# valve_indicatorV1.net
KiCad netlist of a schematic drawn in EAGLE
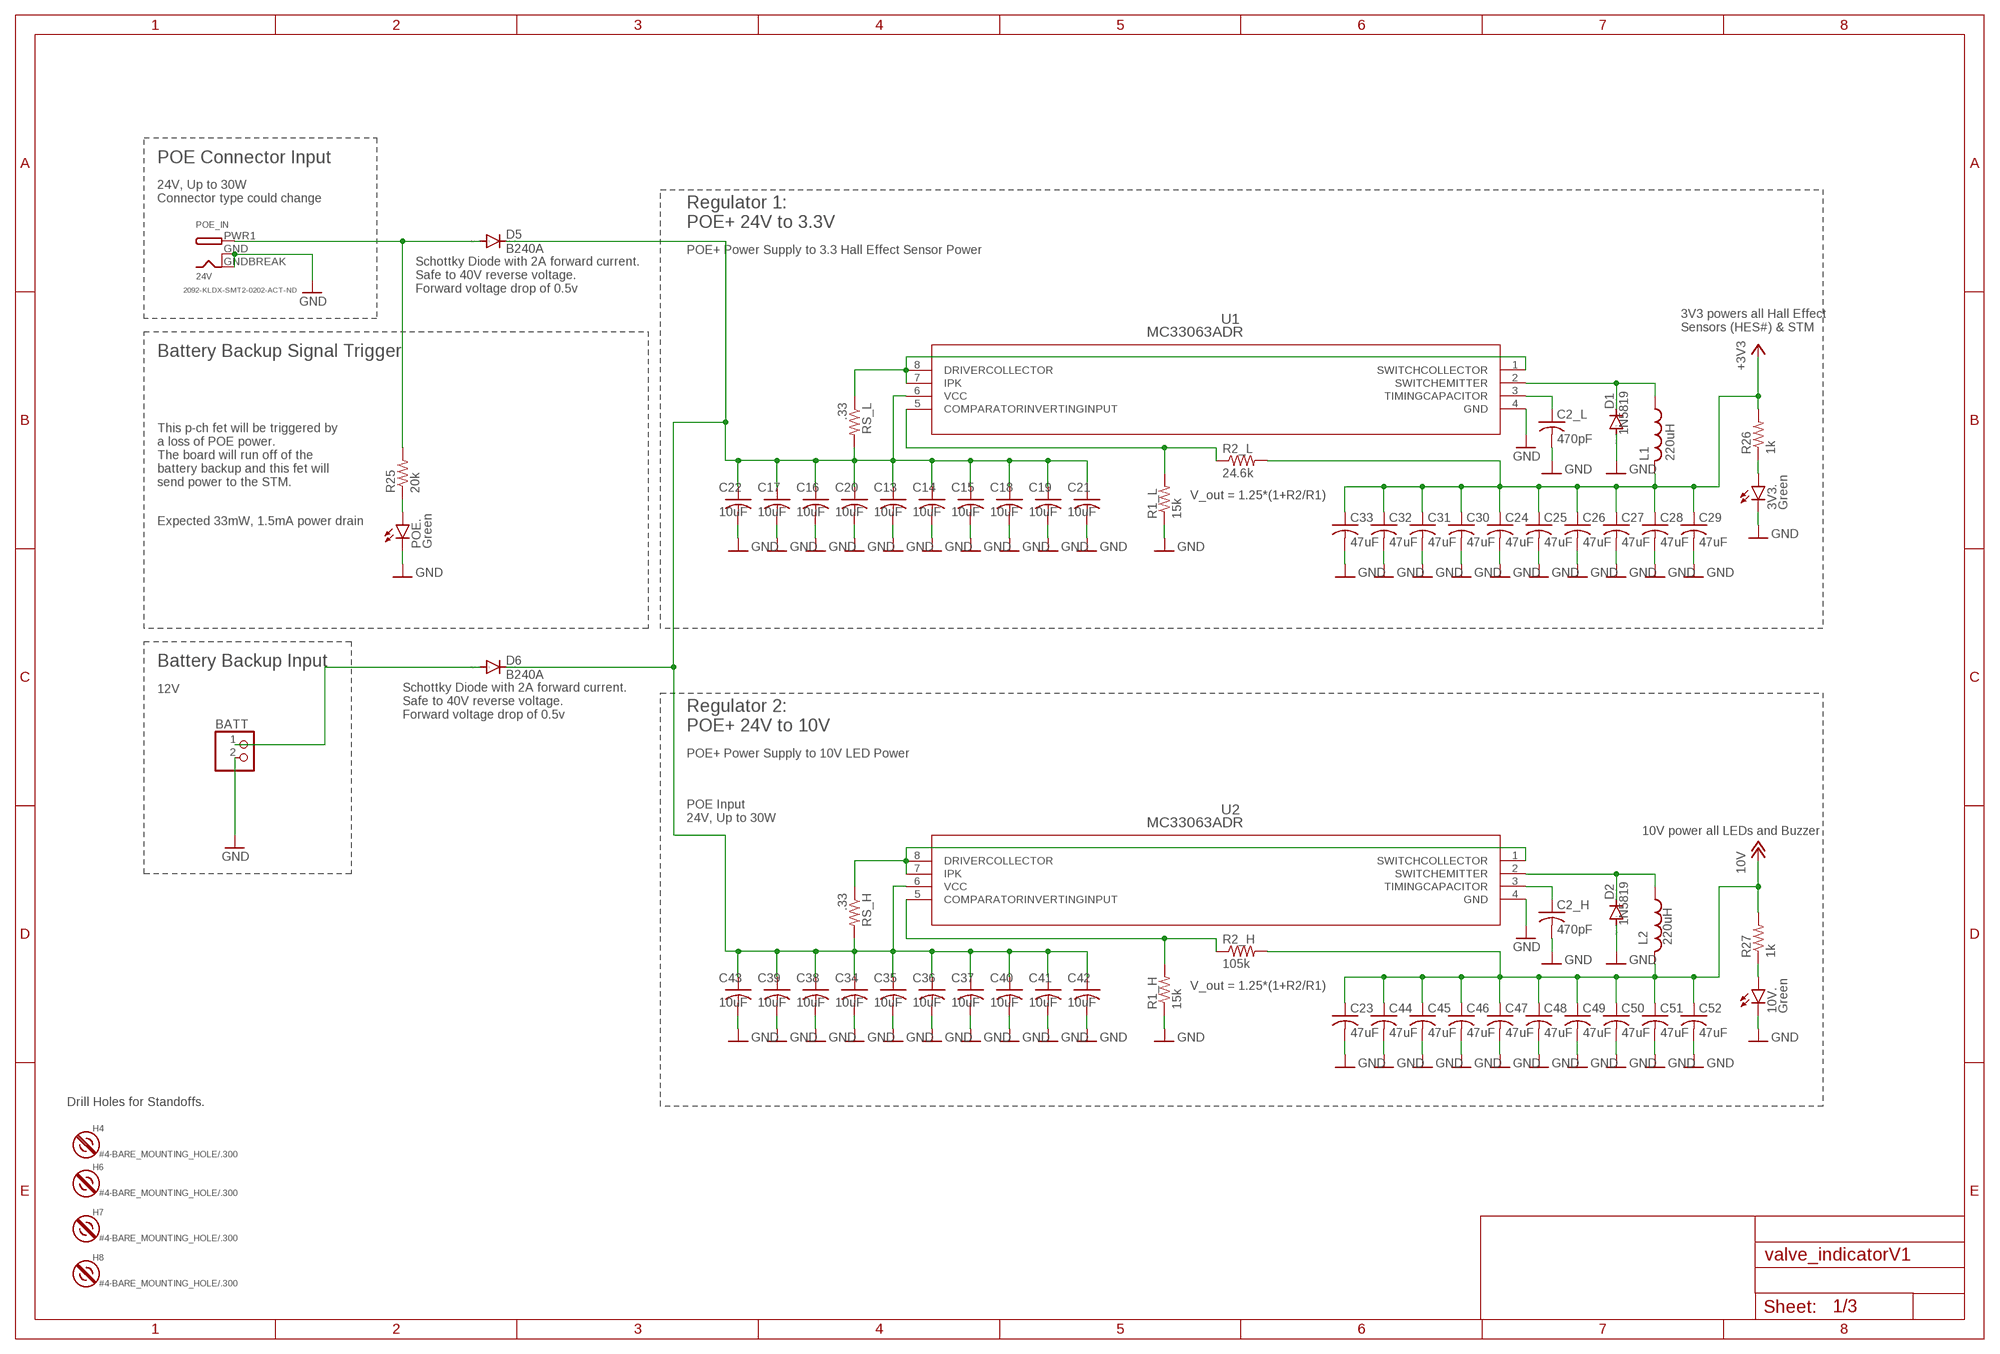
[diagram p0: schematic, sheet 1]
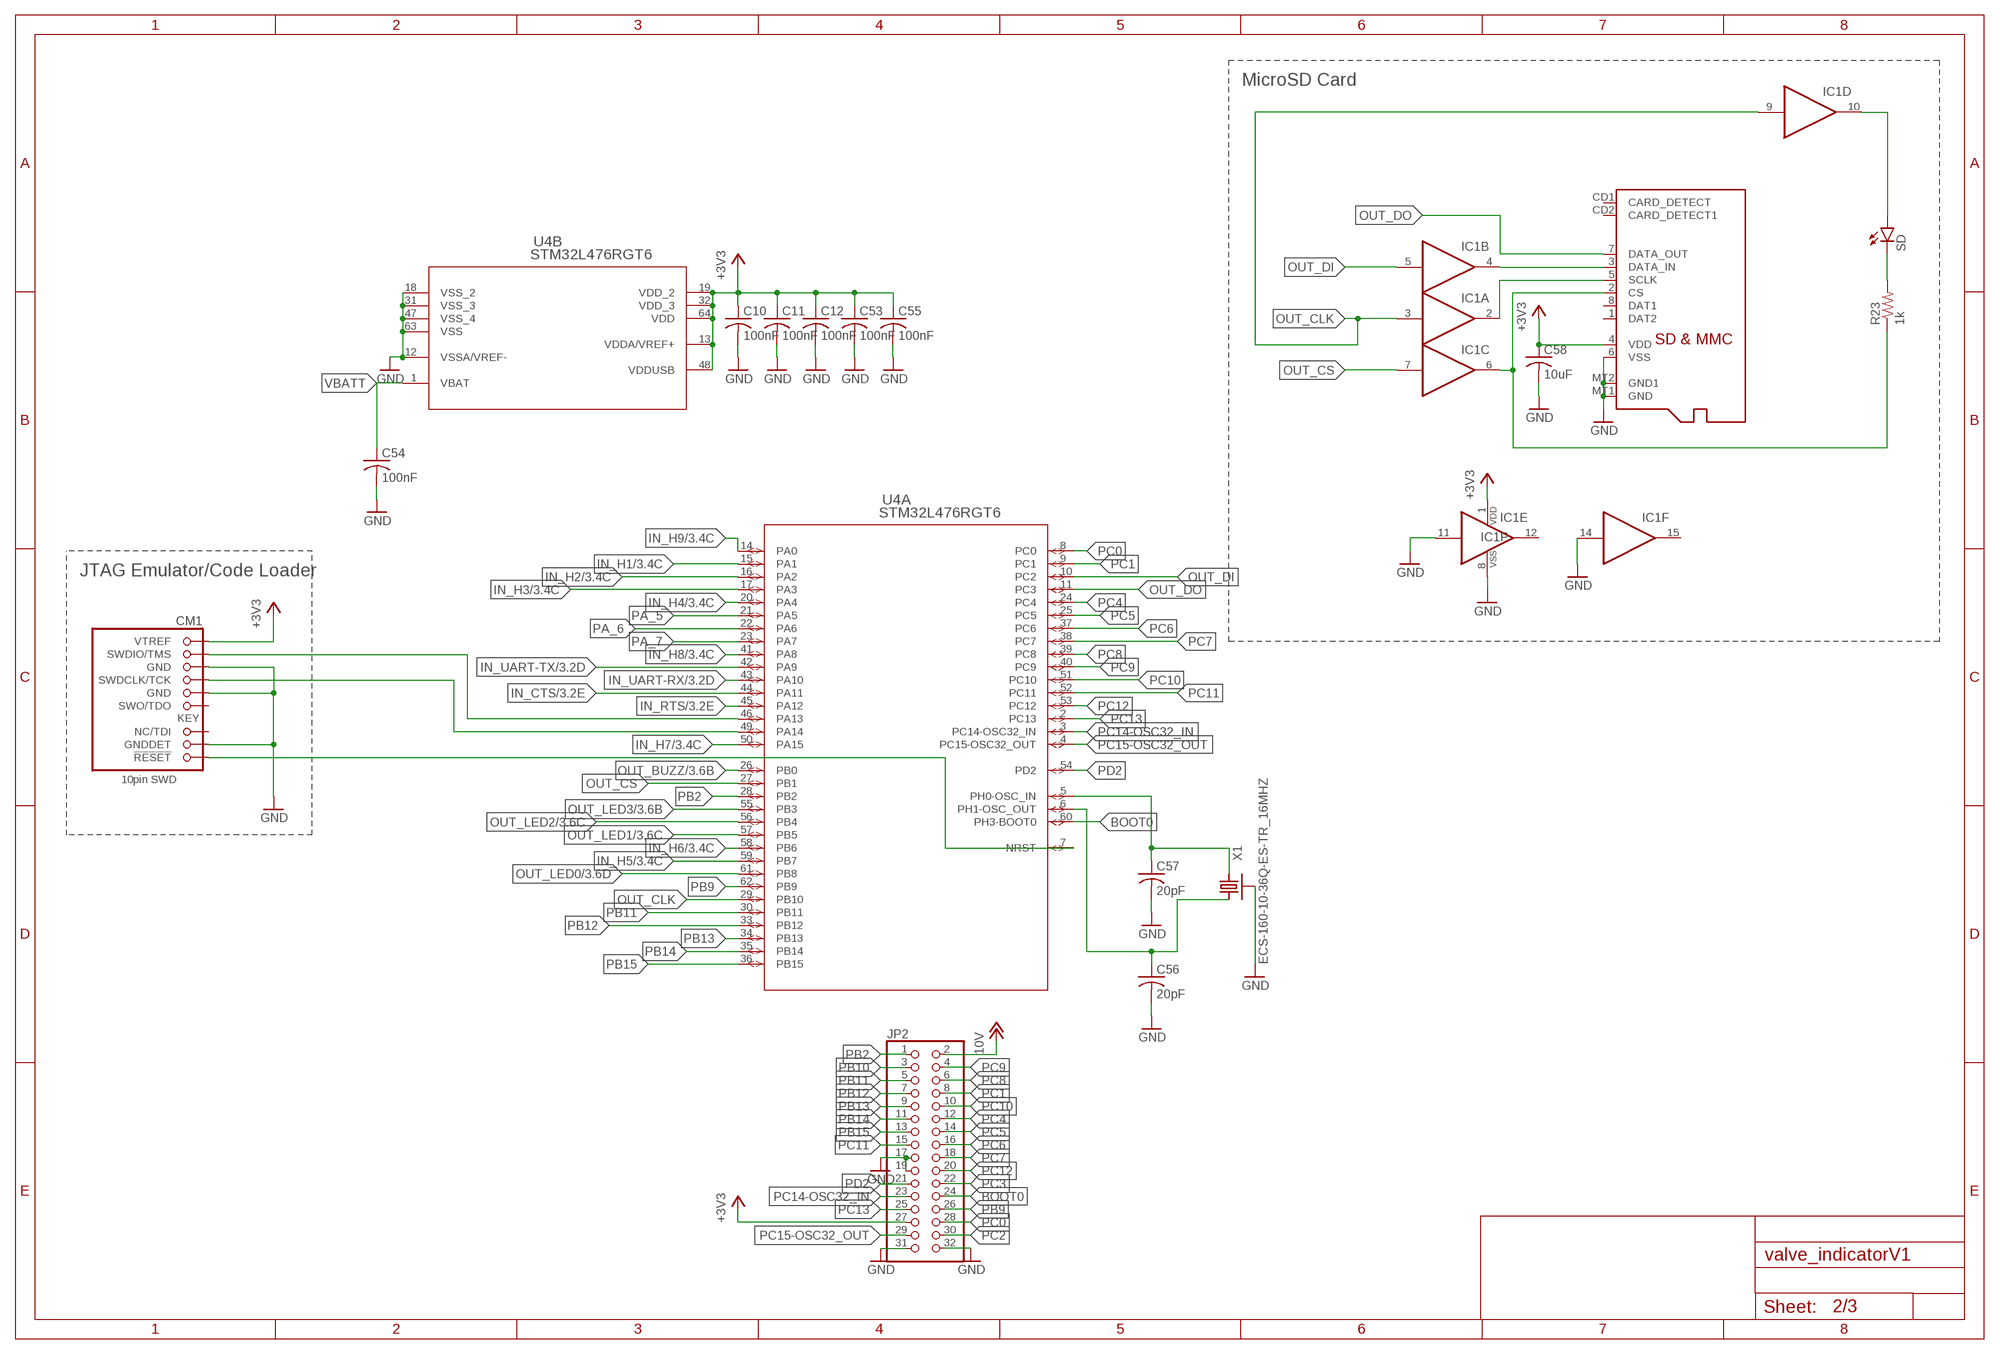
[diagram p1: schematic, sheet 2]
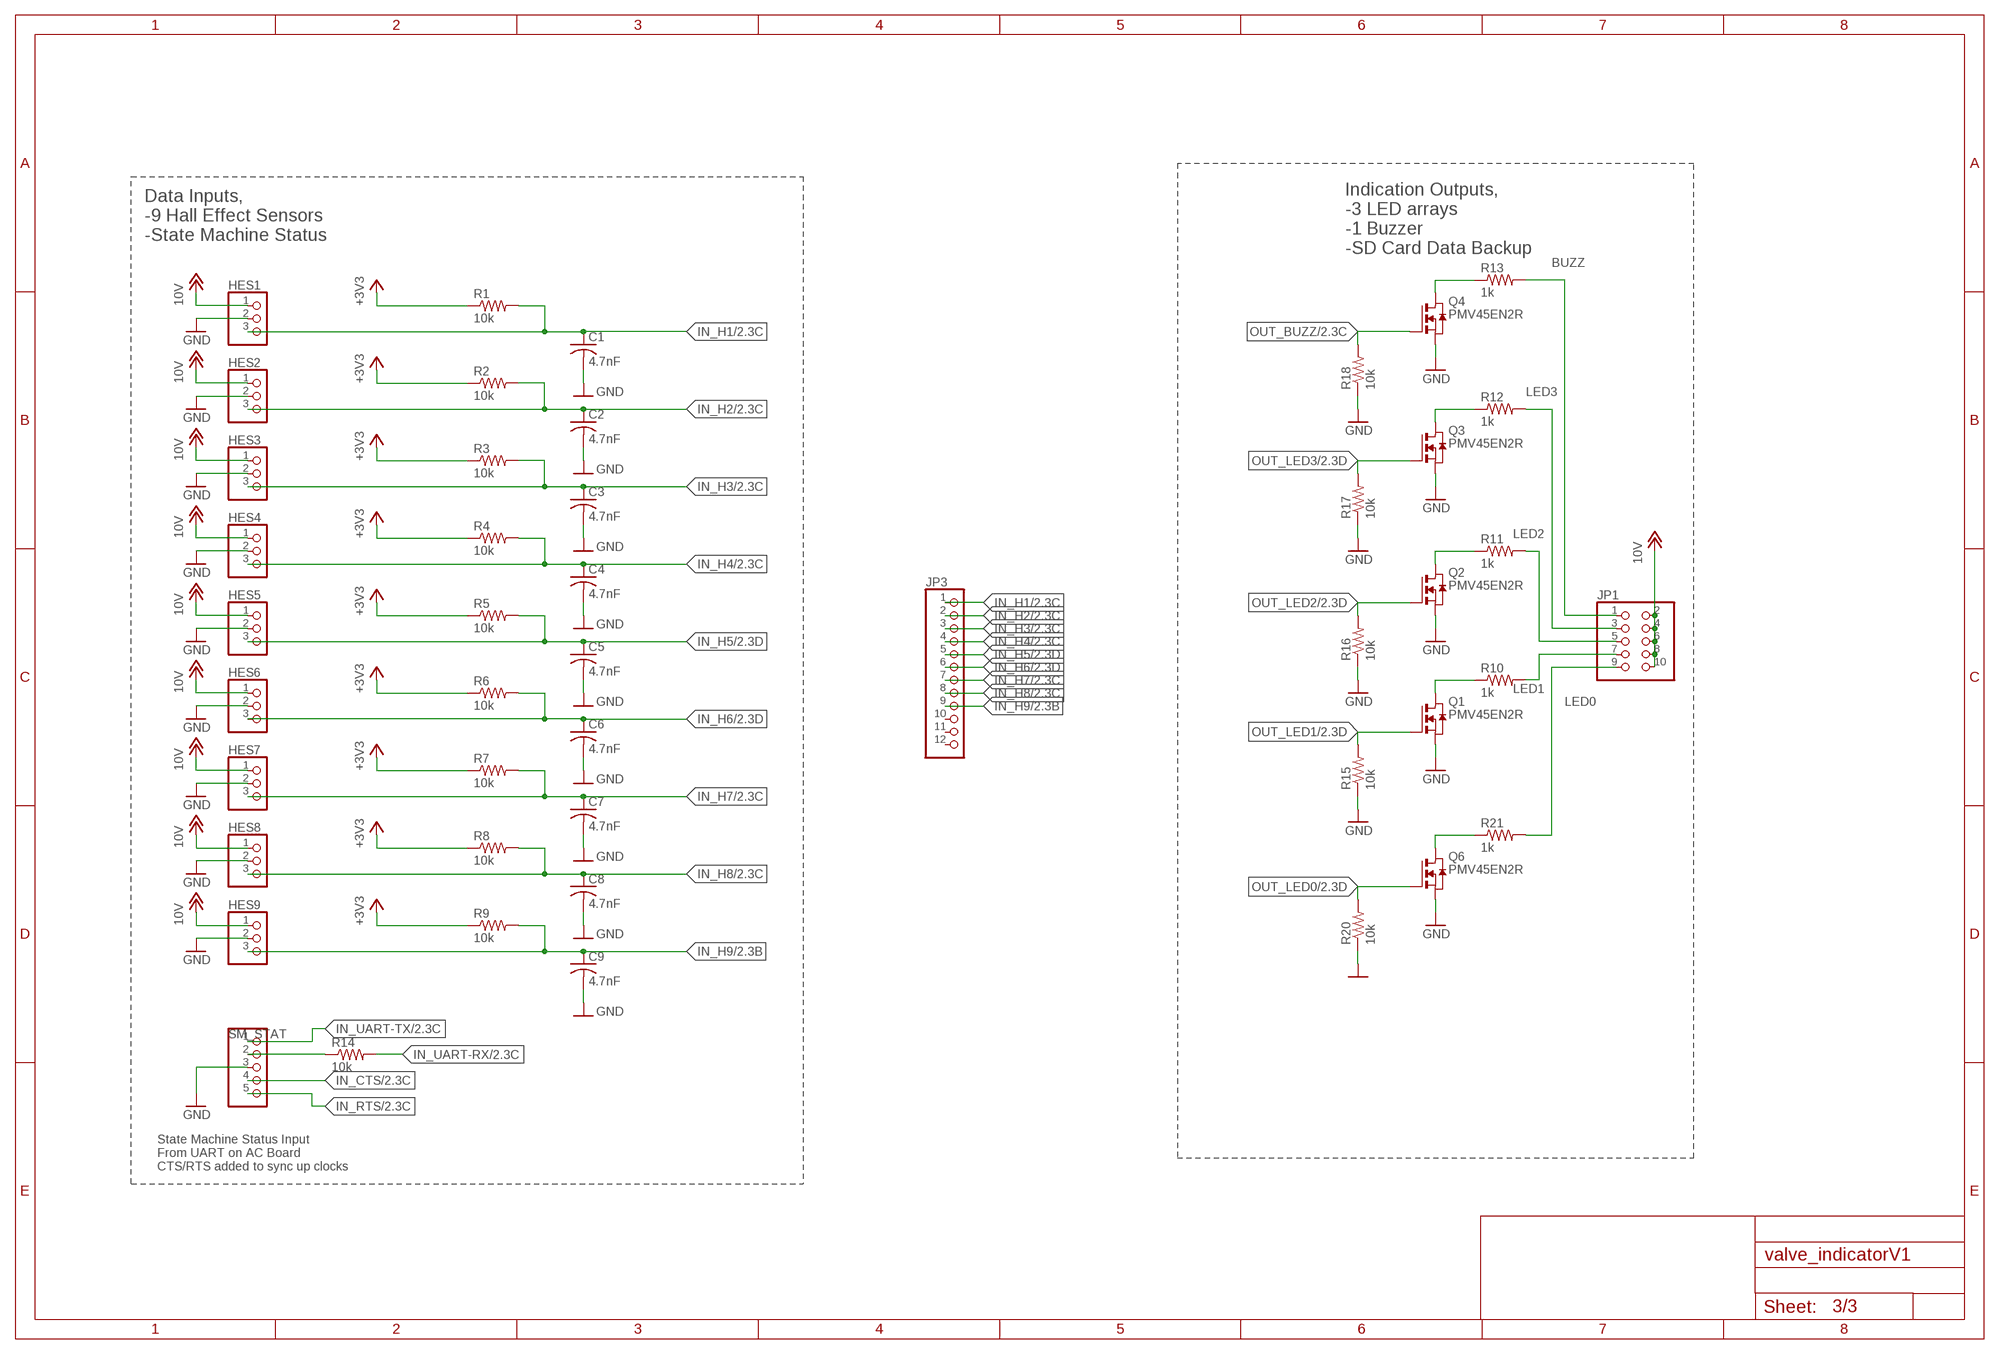
[diagram p2: schematic, sheet 3]

(export (version "E")
  (design (tool "Eeschema 10.0.6"))
  (components
    (comp (ref "C10")
      (value "100nF")
      (footprint "eagle-import:C0603K")
      (fields (field (name "MFR") " Samsung Electro-Mechanics") (field (name "MPN") "CL10B104KA8NNNC"))
      (libsource (lib "eagle-import") (part "C-USC0603K"))
    )
    (comp (ref "C11")
      (value "100nF")
      (footprint "eagle-import:C0603K")
      (fields (field (name "MFR") " Samsung Electro-Mechanics") (field (name "MPN") "CL10B104KA8NNNC"))
      (libsource (lib "eagle-import") (part "C-USC0603K"))
    )
    (comp (ref "C12")
      (value "100nF")
      (footprint "eagle-import:C0603K")
      (fields (field (name "MFR") " Samsung Electro-Mechanics") (field (name "MPN") "CL10B104KA8NNNC"))
      (libsource (lib "eagle-import") (part "C-USC0603K"))
    )
    (comp (ref "C53")
      (value "100nF")
      (footprint "eagle-import:C0603K")
      (fields (field (name "MFR") " Samsung Electro-Mechanics") (field (name "MPN") "CL10B104KA8NNNC"))
      (libsource (lib "eagle-import") (part "C-USC0603K"))
    )
    (comp (ref "C54")
      (value "100nF")
      (footprint "eagle-import:C0603K")
      (fields (field (name "MFR") " Samsung Electro-Mechanics") (field (name "MPN") "CL10B104KA8NNNC"))
      (libsource (lib "eagle-import") (part "C-USC0603K"))
    )
    (comp (ref "C55")
      (value "100nF")
      (footprint "eagle-import:C0603K")
      (fields (field (name "MFR") " Samsung Electro-Mechanics") (field (name "MPN") "CL10B104KA8NNNC"))
      (libsource (lib "eagle-import") (part "C-USC0603K"))
    )
    (comp (ref "C56")
      (value "20pF")
      (footprint "eagle-import:C0402K")
      (fields (field (name "MFR") "KEMET") (field (name "MPN") "CBR04C200F5GAC"))
      (libsource (lib "eagle-import") (part "C-USC0402K"))
    )
    (comp (ref "C57")
      (value "20pF")
      (footprint "eagle-import:C0402K")
      (fields (field (name "MFR") "KEMET") (field (name "MPN") "CBR04C200F5GAC"))
      (libsource (lib "eagle-import") (part "C-USC0402K"))
    )
    (comp (ref "C58")
      (value "10uF")
      (footprint "eagle-import:C0805K")
      (fields (field (name "MFR") "Samsung Electro-Mechanics") (field (name "MPN") "CL21A106KPFNNNG"))
      (libsource (lib "eagle-import") (part "C-USC0805K"))
    )
    (comp (ref "CM1")
      (value "FTSH-105-XX-X-DV-K")
      (footprint "eagle-import:CON10_2X5_DUK_FTSH")
      (fields (field (name "MFR") "Samtec Inc.") (field (name "MPN") "FTSH-105-01-F-DV-K-TR"))
      (libsource (lib "eagle-import") (part "FTSH-105-XX-X-DV-K"))
    )
    (comp (ref "IC1")
      (value "4050D")
      (footprint "eagle-import:SO16")
      (fields
        (field (name "MFR") "Texas Instruments")
        (field (name "MPN") "CD74HC4050M")
        (field (name "DIS") "Digi-Key")
        (field (name "DPN") "296-9214-5-ND")
      )
      (libsource (lib "eagle-import") (part "4050D"))
    )
    (comp (ref "JP2")
      (value "PINHD-2X16")
      (footprint "eagle-import:2X16")
      (fields (field (name "MFR") "Sullins Connector Solutions") (field (name "MPN") "PRPC016DAAN-RC"))
      (libsource (lib "eagle-import") (part "PINHD-2X16"))
    )
    (comp (ref "R23")
      (value "1k")
      (footprint "eagle-import:.0603-C-NOSILK")
      (fields (field (name "MFR") "Rohm Semiconductor") (field (name "MPN") "SDR03EZPJ102"))
      (libsource (lib "eagle-import") (part "R-US_0603-C-NOSILK"))
    )
    (comp (ref "SD")
      (value "LEDCHIP-LED0603")
      (footprint "eagle-import:CHIP-LED0603")
      (fields (field (name "MFR") "Dialight") (field (name "MPN") "5988070107F"))
      (libsource (lib "eagle-import") (part "LEDCHIP-LED0603"))
    )
    (comp (ref "U4")
      (value "STM32L476RGT6")
      (footprint "eagle-import:LQFP64-10X10MM_STM")
      (fields
        (field (name "DIS") "Digi-Key")
        (field (name "DPN") "497-15877-ND")
        (field (name "MFR") "STMicroelectronics")
        (field (name "MPN") "STM32L476RGT6")
        (field (name "COPYRIGHT") "Copyright (C) 2018 Accelerated Designs. All rights reserved")
      )
      (libsource (lib "eagle-import") (part "STM32L476RGT6"))
    )
    (comp (ref "X1")
      (value "ECS-160-10-36Q-ES-TR_16MHZ")
      (footprint "eagle-import:2.5X2.0")
      (fields
        (field (name "DIGI-KEY_PART_NUMBER") "XC2181CT-ND")
        (field (name "MANUFACTURER") "ECS Inc.")
        (field (name "MANUFACTURER_PART_NUMBER") "ECS-160-10-36Q-ES-TR")
      )
      (libsource (lib "eagle-import") (part "ECS-160-10-36Q-ES-TR_16MHZ"))
    )
    (comp (ref "X2")
      (value "MICROSD")
      (footprint "eagle-import:MICROSD")
      (fields (field (name "MFR") "GCT ") (field (name "MPN") "MEM2061-01-188-00-A"))
      (libsource (lib "eagle-import") (part "MICROSD"))
    )
    (comp (ref "C1")
      (value "4.7nF")
      (footprint "eagle-import:C0603")
      (fields (field (name "MFR") "TDK Corporation") (field (name "MPN") "C1608C0G1H472J080AA"))
      (libsource (lib "eagle-import") (part "rcl_334_C-USC0603"))
    )
    (comp (ref "C2")
      (value "4.7nF")
      (footprint "eagle-import:C0603K")
      (fields (field (name "MFR") "TDK Corporation") (field (name "MPN") "C1608C0G1H472J080AA"))
      (libsource (lib "eagle-import") (part "C-USC0603K"))
    )
    (comp (ref "C3")
      (value "4.7nF")
      (footprint "eagle-import:C0603K")
      (fields (field (name "MFR") "TDK Corporation") (field (name "MPN") "C1608C0G1H472J080AA"))
      (libsource (lib "eagle-import") (part "C-USC0603K"))
    )
    (comp (ref "C4")
      (value "4.7nF")
      (footprint "eagle-import:C0603K")
      (fields (field (name "MFR") "TDK Corporation") (field (name "MPN") "C1608C0G1H472J080AA"))
      (libsource (lib "eagle-import") (part "C-USC0603K"))
    )
    (comp (ref "C5")
      (value "4.7nF")
      (footprint "eagle-import:C0603K")
      (fields (field (name "MFR") "TDK Corporation") (field (name "MPN") "C1608C0G1H472J080AA"))
      (libsource (lib "eagle-import") (part "C-USC0603K"))
    )
    (comp (ref "C6")
      (value "4.7nF")
      (footprint "eagle-import:C0603K")
      (fields (field (name "MFR") "TDK Corporation") (field (name "MPN") "C1608C0G1H472J080AA"))
      (libsource (lib "eagle-import") (part "C-USC0603K"))
    )
    (comp (ref "C7")
      (value "4.7nF")
      (footprint "eagle-import:C0603K")
      (fields (field (name "MFR") "TDK Corporation") (field (name "MPN") "C1608C0G1H472J080AA"))
      (libsource (lib "eagle-import") (part "C-USC0603K"))
    )
    (comp (ref "C8")
      (value "4.7nF")
      (footprint "eagle-import:C0603K")
      (fields (field (name "MFR") "TDK Corporation") (field (name "MPN") "C1608C0G1H472J080AA"))
      (libsource (lib "eagle-import") (part "C-USC0603K"))
    )
    (comp (ref "C9")
      (value "4.7nF")
      (footprint "eagle-import:C0603K")
      (fields (field (name "MFR") "TDK Corporation") (field (name "MPN") "C1608C0G1H472J080AA"))
      (libsource (lib "eagle-import") (part "C-USC0603K"))
    )
    (comp (ref "HES1")
      (value "HES1")
      (footprint "eagle-import:1X03")
      (fields (field (name "MFR") "Molex") (field (name "MPN") "1718570003"))
      (libsource (lib "eagle-import") (part "PINHD-1X3"))
    )
    (comp (ref "HES2")
      (value "HES2")
      (footprint "eagle-import:1X03")
      (fields (field (name "MFR") "Molex") (field (name "MPN") "1718570003"))
      (libsource (lib "eagle-import") (part "PINHD-1X3"))
    )
    (comp (ref "HES3")
      (value "HES3")
      (footprint "eagle-import:1X03")
      (fields (field (name "MFR") "Molex") (field (name "MPN") "1718570003"))
      (libsource (lib "eagle-import") (part "PINHD-1X3"))
    )
    (comp (ref "HES4")
      (value "HES4")
      (footprint "eagle-import:1X03")
      (fields (field (name "MFR") "Molex") (field (name "MPN") "1718570003"))
      (libsource (lib "eagle-import") (part "PINHD-1X3"))
    )
    (comp (ref "HES5")
      (value "HES5")
      (footprint "eagle-import:1X03")
      (fields (field (name "MFR") "Molex") (field (name "MPN") "1718570003"))
      (libsource (lib "eagle-import") (part "PINHD-1X3"))
    )
    (comp (ref "HES6")
      (value "HES6")
      (footprint "eagle-import:1X03")
      (fields (field (name "MFR") "Molex") (field (name "MPN") "1718570003"))
      (libsource (lib "eagle-import") (part "PINHD-1X3"))
    )
    (comp (ref "HES7")
      (value "HES7")
      (footprint "eagle-import:1X03")
      (fields (field (name "MFR") "Molex") (field (name "MPN") "1718570003"))
      (libsource (lib "eagle-import") (part "PINHD-1X3"))
    )
    (comp (ref "HES8")
      (value "HES8")
      (footprint "eagle-import:1X03")
      (fields (field (name "MFR") "Molex") (field (name "MPN") "1718570003"))
      (libsource (lib "eagle-import") (part "PINHD-1X3"))
    )
    (comp (ref "HES9")
      (value "HES9")
      (footprint "eagle-import:1X03")
      (fields (field (name "MFR") "Molex") (field (name "MPN") "1718570003"))
      (libsource (lib "eagle-import") (part "PINHD-1X3"))
    )
    (comp (ref "JP1")
      (value "PINHD-2X5")
      (footprint "eagle-import:2X05")
      (fields (field (name "MFR") "Molex") (field (name "MPN") "AWHW 10A-0202-T"))
      (libsource (lib "eagle-import") (part "PINHD-2X5"))
    )
    (comp (ref "JP3")
      (value "PINHD-1X12")
      (footprint "eagle-import:1X12")
      (fields (field (name "MFR") "Molex") (field (name "MPN") "1718570012"))
      (libsource (lib "eagle-import") (part "PINHD-1X12"))
    )
    (comp (ref "Q1")
      (value "PMV45EN2R")
      (footprint "eagle-import:SOT23")
      (fields
        (field (name "MOUSER_PART_NUMBER") "771-PMV45EN2R")
        (field (name "RS_PART_NUMBER") "1364835P")
        (field (name "MFR") "Nexperia USA Inc.")
      )
      (libsource (lib "eagle-import") (part "PMV45EN2R"))
    )
    (comp (ref "Q2")
      (value "PMV45EN2R")
      (footprint "eagle-import:SOT23")
      (fields
        (field (name "MOUSER_PART_NUMBER") "771-PMV45EN2R")
        (field (name "RS_PART_NUMBER") "1364835P")
        (field (name "MFR") "Nexperia USA Inc.")
      )
      (libsource (lib "eagle-import") (part "PMV45EN2R"))
    )
    (comp (ref "Q3")
      (value "PMV45EN2R")
      (footprint "eagle-import:SOT23")
      (fields
        (field (name "MOUSER_PART_NUMBER") "771-PMV45EN2R")
        (field (name "RS_PART_NUMBER") "1364835P")
        (field (name "MFR") "Nexperia USA Inc.")
      )
      (libsource (lib "eagle-import") (part "PMV45EN2R"))
    )
    (comp (ref "Q4")
      (value "PMV45EN2R")
      (footprint "eagle-import:SOT23")
      (fields
        (field (name "MOUSER_PART_NUMBER") "771-PMV45EN2R")
        (field (name "RS_PART_NUMBER") "1364835P")
        (field (name "MFR") "Nexperia USA Inc.")
      )
      (libsource (lib "eagle-import") (part "PMV45EN2R"))
    )
    (comp (ref "Q6")
      (value "PMV45EN2R")
      (footprint "eagle-import:SOT23")
      (fields
        (field (name "MOUSER_PART_NUMBER") "771-PMV45EN2R")
        (field (name "RS_PART_NUMBER") "1364835P")
        (field (name "MFR") "Nexperia USA Inc.")
      )
      (libsource (lib "eagle-import") (part "PMV45EN2R"))
    )
    (comp (ref "R1")
      (value "10k")
      (footprint "eagle-import:.0603-C-NOSILK")
      (fields (field (name "MFR") "Stackpole Electronics Inc") (field (name "MPN") "RMCF0603FT10K0"))
      (libsource (lib "eagle-import") (part "R-US_0603-C-NOSILK"))
    )
    (comp (ref "R2")
      (value "10k")
      (footprint "eagle-import:.0603-C-NOSILK")
      (fields (field (name "MFR") "Stackpole Electronics Inc") (field (name "MPN") "RMCF0603FT10K0"))
      (libsource (lib "eagle-import") (part "R-US_0603-C-NOSILK"))
    )
    (comp (ref "R3")
      (value "10k")
      (footprint "eagle-import:.0603-C-NOSILK")
      (fields (field (name "MFR") "Stackpole Electronics Inc") (field (name "MPN") "RMCF0603FT10K0"))
      (libsource (lib "eagle-import") (part "R-US_0603-C-NOSILK"))
    )
    (comp (ref "R4")
      (value "10k")
      (footprint "eagle-import:.0603-C-NOSILK")
      (fields (field (name "MFR") "Stackpole Electronics Inc") (field (name "MPN") "RMCF0603FT10K0"))
      (libsource (lib "eagle-import") (part "R-US_0603-C-NOSILK"))
    )
    (comp (ref "R5")
      (value "10k")
      (footprint "eagle-import:.0603-C-NOSILK")
      (fields (field (name "MFR") "Stackpole Electronics Inc") (field (name "MPN") "RMCF0603FT10K0"))
      (libsource (lib "eagle-import") (part "R-US_0603-C-NOSILK"))
    )
    (comp (ref "R6")
      (value "10k")
      (footprint "eagle-import:.0603-C-NOSILK")
      (fields (field (name "MFR") "Stackpole Electronics Inc") (field (name "MPN") "RMCF0603FT10K0"))
      (libsource (lib "eagle-import") (part "R-US_0603-C-NOSILK"))
    )
    (comp (ref "R7")
      (value "10k")
      (footprint "eagle-import:.0603-C-NOSILK")
      (fields (field (name "MFR") "Stackpole Electronics Inc") (field (name "MPN") "RMCF0603FT10K0"))
      (libsource (lib "eagle-import") (part "R-US_0603-C-NOSILK"))
    )
    (comp (ref "R8")
      (value "10k")
      (footprint "eagle-import:.0603-C-NOSILK")
      (fields (field (name "MFR") "Stackpole Electronics Inc") (field (name "MPN") "RMCF0603FT10K0"))
      (libsource (lib "eagle-import") (part "R-US_0603-C-NOSILK"))
    )
    (comp (ref "R9")
      (value "10k")
      (footprint "eagle-import:.0603-C-NOSILK")
      (fields (field (name "MFR") "Stackpole Electronics Inc") (field (name "MPN") "RMCF0603FT10K0"))
      (libsource (lib "eagle-import") (part "R-US_0603-C-NOSILK"))
    )
    (comp (ref "R10")
      (value "1k")
      (footprint "eagle-import:.0603-C-NOSILK")
      (fields (field (name "MFR") "Stackpole Electronics Inc") (field (name "MPN") "RMCF0603JJ1K00"))
      (libsource (lib "eagle-import") (part "R-US_0603-C-NOSILK"))
    )
    (comp (ref "R11")
      (value "1k")
      (footprint "eagle-import:.0603-C-NOSILK")
      (fields (field (name "MFR") "Stackpole Electronics Inc") (field (name "MPN") "RMCF0603JJ1K00"))
      (libsource (lib "eagle-import") (part "R-US_0603-C-NOSILK"))
    )
    (comp (ref "R12")
      (value "1k")
      (footprint "eagle-import:.0603-C-NOSILK")
      (fields (field (name "MFR") "Stackpole Electronics Inc") (field (name "MPN") "RMCF0603JJ1K00"))
      (libsource (lib "eagle-import") (part "R-US_0603-C-NOSILK"))
    )
    (comp (ref "R13")
      (value "1k")
      (footprint "eagle-import:.0603-C-NOSILK")
      (fields (field (name "MFR") "Stackpole Electronics Inc") (field (name "MPN") "RMCF0603JJ1K00"))
      (libsource (lib "eagle-import") (part "R-US_0603-C-NOSILK"))
    )
    (comp (ref "R14")
      (value "10k")
      (footprint "eagle-import:.0603-C-NOSILK")
      (fields (field (name "MFR") "Stackpole Electronics Inc") (field (name "MPN") "RMCF0603FT10K0"))
      (libsource (lib "eagle-import") (part "R-US_0603-C-NOSILK"))
    )
    (comp (ref "R15")
      (value "10k")
      (footprint "eagle-import:.0603-C-NOSILK")
      (fields (field (name "MFR") "Stackpole Electronics Inc") (field (name "MPN") "RMCF0603FT10K0"))
      (libsource (lib "eagle-import") (part "R-US_0603-C-NOSILK"))
    )
    (comp (ref "R16")
      (value "10k")
      (footprint "eagle-import:.0603-C-NOSILK")
      (fields (field (name "MFR") "Stackpole Electronics Inc") (field (name "MPN") "RMCF0603FT10K0"))
      (libsource (lib "eagle-import") (part "R-US_0603-C-NOSILK"))
    )
    (comp (ref "R17")
      (value "10k")
      (footprint "eagle-import:.0603-C-NOSILK")
      (fields (field (name "MFR") "Stackpole Electronics Inc") (field (name "MPN") "RMCF0603FT10K0"))
      (libsource (lib "eagle-import") (part "R-US_0603-C-NOSILK"))
    )
    (comp (ref "R18")
      (value "10k")
      (footprint "eagle-import:.0603-C-NOSILK")
      (fields (field (name "MFR") "Stackpole Electronics Inc") (field (name "MPN") "RMCF0603FT10K0"))
      (libsource (lib "eagle-import") (part "R-US_0603-C-NOSILK"))
    )
    (comp (ref "R20")
      (value "10k")
      (footprint "eagle-import:.0603-C-NOSILK")
      (fields (field (name "MFR") "Stackpole Electronics Inc") (field (name "MPN") "RMCF0603FT10K0"))
      (libsource (lib "eagle-import") (part "R-US_0603-C-NOSILK"))
    )
    (comp (ref "R21")
      (value "1k")
      (footprint "eagle-import:R0603")
      (fields (field (name "MFR") "Stackpole Electronics Inc") (field (name "MPN") "RMCF0603JJ1K00"))
      (libsource (lib "eagle-import") (part "rcl_334_R-US_R0603"))
    )
    (comp (ref "SM_STAT")
      (value "SM_STAT")
      (footprint "eagle-import:1X05")
      (fields (field (name "MFR") "Molex") (field (name "MPN") "AWHW 10A-0202-T"))
      (libsource (lib "eagle-import") (part "PINHD-1X5"))
    )
    (comp (ref "3V3.")
      (value "Green")
      (footprint "eagle-import:CHIP-LED0603")
      (fields (field (name "MFR") "Dialight") (field (name "MPN") "5988070107F"))
      (libsource (lib "eagle-import") (part "LEDCHIP-LED0603"))
    )
    (comp (ref "10V.")
      (value "Green")
      (footprint "eagle-import:CHIP-LED0603")
      (fields (field (name "MFR") "Dialight") (field (name "MPN") "5988070107F"))
      (libsource (lib "eagle-import") (part "LEDCHIP-LED0603"))
    )
    (comp (ref "BATT")
      (value "LED1")
      (footprint "eagle-import:1X02")
      (fields (field (name "MFR") "Molex") (field (name "MPN") "0022232021"))
      (libsource (lib "eagle-import") (part "PINHD-1X2"))
    )
    (comp (ref "C2_H")
      (value "470pF")
      (footprint "eagle-import:C0603K")
      (fields (field (name "MFR") "Walsin Technology Corporation") (field (name "MPN") "0603B471K500CT"))
      (libsource (lib "eagle-import") (part "C-USC0603K"))
    )
    (comp (ref "C2_L")
      (value "470pF")
      (footprint "eagle-import:C0603K")
      (fields (field (name "MFR") "Walsin Technology Corporation") (field (name "MPN") "0603B471K500CT"))
      (libsource (lib "eagle-import") (part "C-USC0603K"))
    )
    (comp (ref "C13")
      (value "10uF")
      (footprint "eagle-import:C1206K")
      (fields (field (name "MFR") "Samsung Electro-Mechanics") (field (name "MPN") "CL31A106KBHNNNE"))
      (libsource (lib "eagle-import") (part "C-USC1206K"))
    )
    (comp (ref "C14")
      (value "10uF")
      (footprint "eagle-import:C1206K")
      (fields (field (name "MFR") "Samsung Electro-Mechanics") (field (name "MPN") "CL31A106KBHNNNE"))
      (libsource (lib "eagle-import") (part "C-USC1206K"))
    )
    (comp (ref "C15")
      (value "10uF")
      (footprint "eagle-import:C1206K")
      (fields (field (name "MFR") "Samsung Electro-Mechanics") (field (name "MPN") "CL31A106KBHNNNE"))
      (libsource (lib "eagle-import") (part "C-USC1206K"))
    )
    (comp (ref "C16")
      (value "10uF")
      (footprint "eagle-import:C1206K")
      (fields (field (name "MFR") "Samsung Electro-Mechanics") (field (name "MPN") "CL31A106KBHNNNE"))
      (libsource (lib "eagle-import") (part "C-USC1206K"))
    )
    (comp (ref "C17")
      (value "10uF")
      (footprint "eagle-import:C1206K")
      (fields (field (name "MFR") "Samsung Electro-Mechanics") (field (name "MPN") "CL31A106KBHNNNE"))
      (libsource (lib "eagle-import") (part "C-USC1206K"))
    )
    (comp (ref "C18")
      (value "10uF")
      (footprint "eagle-import:C1206K")
      (fields (field (name "MFR") "Samsung Electro-Mechanics") (field (name "MPN") "CL31A106KBHNNNE"))
      (libsource (lib "eagle-import") (part "C-USC1206K"))
    )
    (comp (ref "C19")
      (value "10uF")
      (footprint "eagle-import:C1206K")
      (fields (field (name "MFR") "Samsung Electro-Mechanics") (field (name "MPN") "CL31A106KBHNNNE"))
      (libsource (lib "eagle-import") (part "C-USC1206K"))
    )
    (comp (ref "C20")
      (value "10uF")
      (footprint "eagle-import:C1206K")
      (fields (field (name "MFR") "Samsung Electro-Mechanics") (field (name "MPN") "CL31A106KBHNNNE"))
      (libsource (lib "eagle-import") (part "C-USC1206K"))
    )
    (comp (ref "C21")
      (value "10uF")
      (footprint "eagle-import:C1206K")
      (fields (field (name "MFR") "Samsung Electro-Mechanics") (field (name "MPN") "CL31A106KBHNNNE"))
      (libsource (lib "eagle-import") (part "C-USC1206K"))
    )
    (comp (ref "C22")
      (value "10uF")
      (footprint "eagle-import:C1206K")
      (fields (field (name "MFR") "Samsung Electro-Mechanics") (field (name "MPN") "CL31A106KBHNNNE"))
      (libsource (lib "eagle-import") (part "C-USC1206K"))
    )
    (comp (ref "C23")
      (value "47uF")
      (footprint "eagle-import:C1206K")
      (fields (field (name "MFR") "TDK Corporation") (field (name "MPN") "C3216X5R1E476M160AC"))
      (libsource (lib "eagle-import") (part "C-USC1206K"))
    )
    (comp (ref "C24")
      (value "47uF")
      (footprint "eagle-import:C0805K")
      (fields (field (name "MFR") "TDK Corporation") (field (name "MPN") "C2012X5R1A476M125AC"))
      (libsource (lib "eagle-import") (part "C-USC0805K"))
    )
    (comp (ref "C25")
      (value "47uF")
      (footprint "eagle-import:C0805K")
      (fields (field (name "MFR") "TDK Corporation") (field (name "MPN") "C2012X5R1A476M125AC"))
      (libsource (lib "eagle-import") (part "C-USC0805K"))
    )
    (comp (ref "C26")
      (value "47uF")
      (footprint "eagle-import:C0805K")
      (fields (field (name "MFR") "TDK Corporation") (field (name "MPN") "C2012X5R1A476M125AC"))
      (libsource (lib "eagle-import") (part "C-USC0805K"))
    )
    (comp (ref "C27")
      (value "47uF")
      (footprint "eagle-import:C0805K")
      (fields (field (name "MFR") "TDK Corporation") (field (name "MPN") "C2012X5R1A476M125AC"))
      (libsource (lib "eagle-import") (part "C-USC0805K"))
    )
    (comp (ref "C28")
      (value "47uF")
      (footprint "eagle-import:C0805K")
      (fields (field (name "MFR") "TDK Corporation") (field (name "MPN") "C2012X5R1A476M125AC"))
      (libsource (lib "eagle-import") (part "C-USC0805K"))
    )
    (comp (ref "C29")
      (value "47uF")
      (footprint "eagle-import:C0805K")
      (fields (field (name "MFR") "TDK Corporation") (field (name "MPN") "C2012X5R1A476M125AC"))
      (libsource (lib "eagle-import") (part "C-USC0805K"))
    )
    (comp (ref "C30")
      (value "47uF")
      (footprint "eagle-import:C0805K")
      (fields (field (name "MFR") "TDK Corporation") (field (name "MPN") "C2012X5R1A476M125AC"))
      (libsource (lib "eagle-import") (part "C-USC0805K"))
    )
    (comp (ref "C31")
      (value "47uF")
      (footprint "eagle-import:C0805K")
      (fields (field (name "MFR") "TDK Corporation") (field (name "MPN") "C2012X5R1A476M125AC"))
      (libsource (lib "eagle-import") (part "C-USC0805K"))
    )
    (comp (ref "C32")
      (value "47uF")
      (footprint "eagle-import:C0805K")
      (fields (field (name "MFR") "TDK Corporation") (field (name "MPN") "C2012X5R1A476M125AC"))
      (libsource (lib "eagle-import") (part "C-USC0805K"))
    )
    (comp (ref "C33")
      (value "47uF")
      (footprint "eagle-import:C0805K")
      (fields (field (name "MFR") "TDK Corporation") (field (name "MPN") "C2012X5R1A476M125AC"))
      (libsource (lib "eagle-import") (part "C-USC0805K"))
    )
    (comp (ref "C34")
      (value "10uF")
      (footprint "eagle-import:C0805K")
      (fields (field (name "MFR") "Murata Electronics") (field (name "MPN") "GRM21BR61H106ME43L"))
      (libsource (lib "eagle-import") (part "C-USC0805K"))
    )
    (comp (ref "C35")
      (value "10uF")
      (footprint "eagle-import:C0805K")
      (fields (field (name "MFR") "Murata Electronics") (field (name "MPN") "GRM21BR61H106ME43L"))
      (libsource (lib "eagle-import") (part "C-USC0805K"))
    )
    (comp (ref "C36")
      (value "10uF")
      (footprint "eagle-import:C0805K")
      (fields (field (name "MFR") "Murata Electronics") (field (name "MPN") "GRM21BR61H106ME43L"))
      (libsource (lib "eagle-import") (part "C-USC0805K"))
    )
    (comp (ref "C37")
      (value "10uF")
      (footprint "eagle-import:C0805K")
      (fields (field (name "MFR") "Murata Electronics") (field (name "MPN") "GRM21BR61H106ME43L"))
      (libsource (lib "eagle-import") (part "C-USC0805K"))
    )
    (comp (ref "C38")
      (value "10uF")
      (footprint "eagle-import:C0805K")
      (fields (field (name "MFR") "Murata Electronics") (field (name "MPN") "GRM21BR61H106ME43L"))
      (libsource (lib "eagle-import") (part "C-USC0805K"))
    )
    (comp (ref "C39")
      (value "10uF")
      (footprint "eagle-import:C0805K")
      (fields (field (name "MFR") "Murata Electronics") (field (name "MPN") "GRM21BR61H106ME43L"))
      (libsource (lib "eagle-import") (part "C-USC0805K"))
    )
    (comp (ref "C40")
      (value "10uF")
      (footprint "eagle-import:C0805K")
      (fields (field (name "MFR") "Murata Electronics") (field (name "MPN") "GRM21BR61H106ME43L"))
      (libsource (lib "eagle-import") (part "C-USC0805K"))
    )
    (comp (ref "C41")
      (value "10uF")
      (footprint "eagle-import:C0805K")
      (fields (field (name "MFR") "Murata Electronics") (field (name "MPN") "GRM21BR61H106ME43L"))
      (libsource (lib "eagle-import") (part "C-USC0805K"))
    )
    (comp (ref "C42")
      (value "10uF")
      (footprint "eagle-import:C0805K")
      (fields (field (name "MFR") "Murata Electronics") (field (name "MPN") "GRM21BR61H106ME43L"))
      (libsource (lib "eagle-import") (part "C-USC0805K"))
    )
    (comp (ref "C43")
      (value "10uF")
      (footprint "eagle-import:C0805K")
      (fields (field (name "MFR") "Murata Electronics") (field (name "MPN") "GRM21BR61H106ME43L"))
      (libsource (lib "eagle-import") (part "C-USC0805K"))
    )
    (comp (ref "C44")
      (value "47uF")
      (footprint "eagle-import:C1206K")
      (fields (field (name "MFR") "TDK Corporation") (field (name "MPN") "C3216X5R1E476M160AC"))
      (libsource (lib "eagle-import") (part "C-USC1206K"))
    )
    (comp (ref "C45")
      (value "47uF")
      (footprint "eagle-import:C1206K")
      (fields (field (name "MFR") "TDK Corporation") (field (name "MPN") "C3216X5R1E476M160AC"))
      (libsource (lib "eagle-import") (part "C-USC1206K"))
    )
    (comp (ref "C46")
      (value "47uF")
      (footprint "eagle-import:C1206K")
      (fields (field (name "MFR") "TDK Corporation") (field (name "MPN") "C3216X5R1E476M160AC"))
      (libsource (lib "eagle-import") (part "C-USC1206K"))
    )
    (comp (ref "C47")
      (value "47uF")
      (footprint "eagle-import:C1206K")
      (fields (field (name "MFR") "TDK Corporation") (field (name "MPN") "C3216X5R1E476M160AC"))
      (libsource (lib "eagle-import") (part "C-USC1206K"))
    )
    (comp (ref "C48")
      (value "47uF")
      (footprint "eagle-import:C1206K")
      (fields (field (name "MFR") "TDK Corporation") (field (name "MPN") "C3216X5R1E476M160AC"))
      (libsource (lib "eagle-import") (part "C-USC1206K"))
    )
    (comp (ref "C49")
      (value "47uF")
      (footprint "eagle-import:C1206K")
      (fields (field (name "MFR") "TDK Corporation") (field (name "MPN") "C3216X5R1E476M160AC"))
      (libsource (lib "eagle-import") (part "C-USC1206K"))
    )
    (comp (ref "C50")
      (value "47uF")
      (footprint "eagle-import:C1206K")
      (fields (field (name "MFR") "TDK Corporation") (field (name "MPN") "C3216X5R1E476M160AC"))
      (libsource (lib "eagle-import") (part "C-USC1206K"))
    )
    (comp (ref "C51")
      (value "47uF")
      (footprint "eagle-import:C1206K")
      (fields (field (name "MFR") "TDK Corporation") (field (name "MPN") "C3216X5R1E476M160AC"))
      (libsource (lib "eagle-import") (part "C-USC1206K"))
    )
    (comp (ref "C52")
      (value "47uF")
      (footprint "eagle-import:C1206K")
      (fields (field (name "MFR") "TDK Corporation") (field (name "MPN") "C3216X5R1E476M160AC"))
      (libsource (lib "eagle-import") (part "C-USC1206K"))
    )
    (comp (ref "D1")
      (value "1N5819")
      (footprint "eagle-import:SOD123")
      (fields (field (name "MFR") "Diodes Incorporated") (field (name "MPN") "1N5819HW-7-F"))
      (libsource (lib "eagle-import") (part "DIODE-SOD123"))
    )
    (comp (ref "D2")
      (value "1N5819")
      (footprint "eagle-import:SOD123")
      (fields (field (name "MFR") "Diodes Incorporated") (field (name "MPN") "1N5819HW-7-F"))
      (libsource (lib "eagle-import") (part "DIODE-SOD123"))
    )
    (comp (ref "D5")
      (value "B240A")
      (footprint "eagle-import:DO214AC")
      (fields (field (name "MFR") "Diodes Incorporated") (field (name "MPN") "B240A-13-F"))
      (libsource (lib "eagle-import") (part "DIODE-DO214AC"))
    )
    (comp (ref "D6")
      (value "B240A")
      (footprint "eagle-import:DO214AC")
      (fields (field (name "MFR") "Diodes Incorporated") (field (name "MPN") "B240A-13-F"))
      (libsource (lib "eagle-import") (part "DIODE-DO214AC"))
    )
    (comp (ref "H4")
      (value "#4-BARE_MOUNTING_HOLE/.300")
      (footprint "eagle-import:#4_.300-BARE+STD_NUT_OR_STAR_WASHER")
      (libsource (lib "eagle-import") (part "#4-BARE_MOUNTING_HOLE/.300"))
    )
    (comp (ref "H6")
      (value "#4-BARE_MOUNTING_HOLE/.300")
      (footprint "eagle-import:#4_.300-BARE+STD_NUT_OR_STAR_WASHER")
      (libsource (lib "eagle-import") (part "#4-BARE_MOUNTING_HOLE/.300"))
    )
    (comp (ref "H7")
      (value "#4-BARE_MOUNTING_HOLE/.300")
      (footprint "eagle-import:#4_.300-BARE+STD_NUT_OR_STAR_WASHER")
      (libsource (lib "eagle-import") (part "#4-BARE_MOUNTING_HOLE/.300"))
    )
    (comp (ref "H8")
      (value "#4-BARE_MOUNTING_HOLE/.300")
      (footprint "eagle-import:#4_.300-BARE+STD_NUT_OR_STAR_WASHER")
      (libsource (lib "eagle-import") (part "#4-BARE_MOUNTING_HOLE/.300"))
    )
    (comp (ref "L1")
      (value "220uH")
      (footprint "eagle-import:0207_7")
      (fields (field (name "MFR") "Murata Power Solutions Inc. ") (field (name "MPN") "12RS224C"))
      (libsource (lib "eagle-import") (part "L-US0207/7"))
    )
    (comp (ref "L2")
      (value "220uH")
      (footprint "eagle-import:0207_7")
      (fields (field (name "MFR") "Murata Power Solutions Inc. ") (field (name "MPN") "12RS224C"))
      (libsource (lib "eagle-import") (part "L-US0207/7"))
    )
    (comp (ref "POE.")
      (value "Green")
      (footprint "eagle-import:CHIP-LED0603")
      (fields (field (name "MFR") "Dialight") (field (name "MPN") "5988070107F"))
      (libsource (lib "eagle-import") (part "LEDCHIP-LED0603"))
    )
    (comp (ref "POE_IN")
      (value "24V")
      (footprint "eagle-import:DCJACK_2MM_SMT")
      (fields (field (name "MFR") "Kycon, Inc.") (field (name "MPN") "KLDX-SMT2-0202-ATR"))
      (libsource (lib "eagle-import") (part "DCBARRELSMT"))
    )
    (comp (ref "R1_H")
      (value "15k")
      (footprint "eagle-import:.0805-C-NOSILK")
      (fields (field (name "MFR") "Vishay Dale") (field (name "MPN") "CRCW080515K0FKEAHP"))
      (libsource (lib "eagle-import") (part "R-US_0805-C-NOSILK"))
    )
    (comp (ref "R1_L")
      (value "15k")
      (footprint "eagle-import:.0805-C-NOSILK")
      (fields (field (name "MFR") "Vishay Dale") (field (name "MPN") "CRCW080515K0FKEAHP"))
      (libsource (lib "eagle-import") (part "R-US_0805-C-NOSILK"))
    )
    (comp (ref "R2_H")
      (value "105k")
      (footprint "eagle-import:R1210")
      (fields (field (name "MFR") "Panasonic Electronic Components") (field (name "MPN") "ERJ-14NF1053U"))
      (libsource (lib "eagle-import") (part "R-US_R1210"))
    )
    (comp (ref "R2_L")
      (value "24.6k")
      (footprint "eagle-import:.0805-C-NOSILK")
      (fields (field (name "MFR") "Vishay Dale") (field (name "MPN") "CRCW080524K9FKEAHP"))
      (libsource (lib "eagle-import") (part "R-US_0805-C-NOSILK"))
    )
    (comp (ref "R25")
      (value "20k")
      (footprint "eagle-import:.0603-C-NOSILK")
      (fields (field (name "MFR") "Rohm Semiconductor") (field (name "MPN") "ESR03EZPJ203"))
      (libsource (lib "eagle-import") (part "R-US_0603-C-NOSILK"))
    )
    (comp (ref "R26")
      (value "1k")
      (footprint "eagle-import:.0603-C-NOSILK")
      (fields (field (name "MFR") "Rohm Semiconductor") (field (name "MPN") "SDR03EZPJ102"))
      (libsource (lib "eagle-import") (part "R-US_0603-C-NOSILK"))
    )
    (comp (ref "R27")
      (value "1k")
      (footprint "eagle-import:.0603-C-NOSILK")
      (fields (field (name "MFR") "Rohm Semiconductor") (field (name "MPN") "SDR03EZPJ102"))
      (libsource (lib "eagle-import") (part "R-US_0603-C-NOSILK"))
    )
    (comp (ref "RS_H")
      (value ".33")
      (footprint "eagle-import:.0603-C-NOSILK")
      (fields (field (name "MFR") "Panasonic Electronic Components") (field (name "MPN") "ERJ-3RQFR33V"))
      (libsource (lib "eagle-import") (part "R-US_0603-C-NOSILK"))
    )
    (comp (ref "RS_L")
      (value ".33")
      (footprint "eagle-import:.0603-C-NOSILK")
      (fields (field (name "MFR") "Panasonic Electronic Components") (field (name "MPN") "ERJ-3RQFR33V"))
      (libsource (lib "eagle-import") (part "R-US_0603-C-NOSILK"))
    )
    (comp (ref "U1")
      (value "MC33063ADR")
      (footprint "eagle-import:D8")
      (fields
        (field (name "GENERIC_PART_NUMBER") "MC33063A")
        (field (name "MANUFACTURER") "Texas Instruments")
      )
      (libsource (lib "eagle-import") (part "MC33063ADR"))
    )
    (comp (ref "U2")
      (value "MC33063ADR")
      (footprint "eagle-import:D8")
      (fields
        (field (name "GENERIC_PART_NUMBER") "MC33063A")
        (field (name "MANUFACTURER") "Texas Instruments")
      )
      (libsource (lib "eagle-import") (part "MC33063ADR"))
    )
  )
  (nets
    (net (code "1") (name "+3V3") (class "Default")
      (node (ref "C10") (pin "1") (pinfunction "1_1") (pintype "passive"))
      (node (ref "C11") (pin "1") (pinfunction "1_1") (pintype "passive"))
      (node (ref "C12") (pin "1") (pinfunction "1_1") (pintype "passive"))
      (node (ref "C24") (pin "1") (pinfunction "1_1") (pintype "passive"))
      (node (ref "C25") (pin "1") (pinfunction "1_1") (pintype "passive"))
      (node (ref "C26") (pin "1") (pinfunction "1_1") (pintype "passive"))
      (node (ref "C27") (pin "1") (pinfunction "1_1") (pintype "passive"))
      (node (ref "C28") (pin "1") (pinfunction "1_1") (pintype "passive"))
      (node (ref "C29") (pin "1") (pinfunction "1_1") (pintype "passive"))
      (node (ref "C30") (pin "1") (pinfunction "1_1") (pintype "passive"))
      (node (ref "C31") (pin "1") (pinfunction "1_1") (pintype "passive"))
      (node (ref "C32") (pin "1") (pinfunction "1_1") (pintype "passive"))
      (node (ref "C33") (pin "1") (pinfunction "1_1") (pintype "passive"))
      (node (ref "C53") (pin "1") (pinfunction "1_1") (pintype "passive"))
      (node (ref "C55") (pin "1") (pinfunction "1_1") (pintype "passive"))
      (node (ref "C58") (pin "1") (pinfunction "1_1") (pintype "passive"))
      (node (ref "CM1") (pin "1") (pinfunction "VTREF_1") (pintype "passive"))
      (node (ref "IC1") (pin "1") (pinfunction "VDD_1") (pintype "power_in"))
      (node (ref "JP2") (pin "27") (pinfunction "27_27") (pintype "passive"))
      (node (ref "L1") (pin "3") (pinfunction "2_3") (pintype "passive"))
      (node (ref "R1") (pin "1") (pinfunction "1_1") (pintype "passive"))
      (node (ref "R2") (pin "1") (pinfunction "1_1") (pintype "passive"))
      (node (ref "R26") (pin "2") (pinfunction "2_2") (pintype "passive"))
      (node (ref "R2_L") (pin "2") (pinfunction "2_2") (pintype "passive"))
      (node (ref "R3") (pin "1") (pinfunction "1_1") (pintype "passive"))
      (node (ref "R4") (pin "1") (pinfunction "1_1") (pintype "passive"))
      (node (ref "R5") (pin "1") (pinfunction "1_1") (pintype "passive"))
      (node (ref "R6") (pin "1") (pinfunction "1_1") (pintype "passive"))
      (node (ref "R7") (pin "1") (pinfunction "1_1") (pintype "passive"))
      (node (ref "R8") (pin "1") (pinfunction "1_1") (pintype "passive"))
      (node (ref "R9") (pin "1") (pinfunction "1_1") (pintype "passive"))
      (node (ref "U4") (pin "13") (pinfunction "VDDA/VREF+_13") (pintype "power_in"))
      (node (ref "U4") (pin "19") (pinfunction "VDD_2_19") (pintype "power_in"))
      (node (ref "U4") (pin "32") (pinfunction "VDD_3_32") (pintype "power_in"))
      (node (ref "U4") (pin "48") (pinfunction "VDDUSB_48") (pintype "power_in"))
      (node (ref "U4") (pin "64") (pinfunction "VDD_64") (pintype "power_in"))
      (node (ref "X2") (pin "4") (pinfunction "VDD_4") (pintype "power_in"))
    )
    (net (code "2") (name "+10V") (class "Default")
      (node (ref "C23") (pin "1") (pinfunction "1_1") (pintype "passive"))
      (node (ref "C44") (pin "1") (pinfunction "1_1") (pintype "passive"))
      (node (ref "C45") (pin "1") (pinfunction "1_1") (pintype "passive"))
      (node (ref "C46") (pin "1") (pinfunction "1_1") (pintype "passive"))
      (node (ref "C47") (pin "1") (pinfunction "1_1") (pintype "passive"))
      (node (ref "C48") (pin "1") (pinfunction "1_1") (pintype "passive"))
      (node (ref "C49") (pin "1") (pinfunction "1_1") (pintype "passive"))
      (node (ref "C50") (pin "1") (pinfunction "1_1") (pintype "passive"))
      (node (ref "C51") (pin "1") (pinfunction "1_1") (pintype "passive"))
      (node (ref "C52") (pin "1") (pinfunction "1_1") (pintype "passive"))
      (node (ref "HES1") (pin "1") (pinfunction "1_1") (pintype "passive"))
      (node (ref "HES2") (pin "1") (pinfunction "1_1") (pintype "passive"))
      (node (ref "HES3") (pin "1") (pinfunction "1_1") (pintype "passive"))
      (node (ref "HES4") (pin "1") (pinfunction "1_1") (pintype "passive"))
      (node (ref "HES5") (pin "1") (pinfunction "1_1") (pintype "passive"))
      (node (ref "HES6") (pin "1") (pinfunction "1_1") (pintype "passive"))
      (node (ref "HES7") (pin "1") (pinfunction "1_1") (pintype "passive"))
      (node (ref "HES8") (pin "1") (pinfunction "1_1") (pintype "passive"))
      (node (ref "HES9") (pin "1") (pinfunction "1_1") (pintype "passive"))
      (node (ref "JP1") (pin "10") (pinfunction "10_10") (pintype "passive"))
      (node (ref "JP1") (pin "2") (pinfunction "2_2") (pintype "passive"))
      (node (ref "JP1") (pin "4") (pinfunction "4_4") (pintype "passive"))
      (node (ref "JP1") (pin "6") (pinfunction "6_6") (pintype "passive"))
      (node (ref "JP1") (pin "8") (pinfunction "8_8") (pintype "passive"))
      (node (ref "JP2") (pin "2") (pinfunction "2_2") (pintype "passive"))
      (node (ref "L2") (pin "3") (pinfunction "2_3") (pintype "passive"))
      (node (ref "R27") (pin "2") (pinfunction "2_2") (pintype "passive"))
      (node (ref "R2_H") (pin "2") (pinfunction "2_2") (pintype "passive"))
    )
    (net (code "3") (name "BOOT0") (class "Default")
      (node (ref "JP2") (pin "24") (pinfunction "24_24") (pintype "passive"))
      (node (ref "U4") (pin "60") (pinfunction "PH3-BOOT0_60") (pintype "bidirectional"))
    )
    (net (code "4") (name "BUZZ") (class "Default")
      (node (ref "JP1") (pin "1") (pinfunction "1_1") (pintype "passive"))
      (node (ref "R13") (pin "2") (pinfunction "2_2") (pintype "passive"))
    )
    (net (code "5") (name "GND") (class "Default")
      (node (ref "10V.") (pin "C") (pinfunction "C_C") (pintype "passive"))
      (node (ref "3V3.") (pin "C") (pinfunction "C_C") (pintype "passive"))
      (node (ref "BATT") (pin "2") (pinfunction "2_2") (pintype "passive"))
      (node (ref "C1") (pin "2") (pinfunction "2_2") (pintype "passive"))
      (node (ref "C10") (pin "2") (pinfunction "2_2") (pintype "passive"))
      (node (ref "C11") (pin "2") (pinfunction "2_2") (pintype "passive"))
      (node (ref "C12") (pin "2") (pinfunction "2_2") (pintype "passive"))
      (node (ref "C13") (pin "2") (pinfunction "2_2") (pintype "passive"))
      (node (ref "C14") (pin "2") (pinfunction "2_2") (pintype "passive"))
      (node (ref "C15") (pin "2") (pinfunction "2_2") (pintype "passive"))
      (node (ref "C16") (pin "2") (pinfunction "2_2") (pintype "passive"))
      (node (ref "C17") (pin "2") (pinfunction "2_2") (pintype "passive"))
      (node (ref "C18") (pin "2") (pinfunction "2_2") (pintype "passive"))
      (node (ref "C19") (pin "2") (pinfunction "2_2") (pintype "passive"))
      (node (ref "C2") (pin "2") (pinfunction "2_2") (pintype "passive"))
      (node (ref "C20") (pin "2") (pinfunction "2_2") (pintype "passive"))
      (node (ref "C21") (pin "2") (pinfunction "2_2") (pintype "passive"))
      (node (ref "C22") (pin "2") (pinfunction "2_2") (pintype "passive"))
      (node (ref "C23") (pin "2") (pinfunction "2_2") (pintype "passive"))
      (node (ref "C24") (pin "2") (pinfunction "2_2") (pintype "passive"))
      (node (ref "C25") (pin "2") (pinfunction "2_2") (pintype "passive"))
      (node (ref "C26") (pin "2") (pinfunction "2_2") (pintype "passive"))
      (node (ref "C27") (pin "2") (pinfunction "2_2") (pintype "passive"))
      (node (ref "C28") (pin "2") (pinfunction "2_2") (pintype "passive"))
      (node (ref "C29") (pin "2") (pinfunction "2_2") (pintype "passive"))
      (node (ref "C2_H") (pin "2") (pinfunction "2_2") (pintype "passive"))
      (node (ref "C2_L") (pin "2") (pinfunction "2_2") (pintype "passive"))
      (node (ref "C3") (pin "2") (pinfunction "2_2") (pintype "passive"))
      (node (ref "C30") (pin "2") (pinfunction "2_2") (pintype "passive"))
      (node (ref "C31") (pin "2") (pinfunction "2_2") (pintype "passive"))
      (node (ref "C32") (pin "2") (pinfunction "2_2") (pintype "passive"))
      (node (ref "C33") (pin "2") (pinfunction "2_2") (pintype "passive"))
      (node (ref "C34") (pin "2") (pinfunction "2_2") (pintype "passive"))
      (node (ref "C35") (pin "2") (pinfunction "2_2") (pintype "passive"))
      (node (ref "C36") (pin "2") (pinfunction "2_2") (pintype "passive"))
      (node (ref "C37") (pin "2") (pinfunction "2_2") (pintype "passive"))
      (node (ref "C38") (pin "2") (pinfunction "2_2") (pintype "passive"))
      (node (ref "C39") (pin "2") (pinfunction "2_2") (pintype "passive"))
      (node (ref "C4") (pin "2") (pinfunction "2_2") (pintype "passive"))
      (node (ref "C40") (pin "2") (pinfunction "2_2") (pintype "passive"))
      (node (ref "C41") (pin "2") (pinfunction "2_2") (pintype "passive"))
      (node (ref "C42") (pin "2") (pinfunction "2_2") (pintype "passive"))
      (node (ref "C43") (pin "2") (pinfunction "2_2") (pintype "passive"))
      (node (ref "C44") (pin "2") (pinfunction "2_2") (pintype "passive"))
      (node (ref "C45") (pin "2") (pinfunction "2_2") (pintype "passive"))
      (node (ref "C46") (pin "2") (pinfunction "2_2") (pintype "passive"))
      (node (ref "C47") (pin "2") (pinfunction "2_2") (pintype "passive"))
      (node (ref "C48") (pin "2") (pinfunction "2_2") (pintype "passive"))
      (node (ref "C49") (pin "2") (pinfunction "2_2") (pintype "passive"))
      (node (ref "C5") (pin "2") (pinfunction "2_2") (pintype "passive"))
      (node (ref "C50") (pin "2") (pinfunction "2_2") (pintype "passive"))
      (node (ref "C51") (pin "2") (pinfunction "2_2") (pintype "passive"))
      (node (ref "C52") (pin "2") (pinfunction "2_2") (pintype "passive"))
      (node (ref "C53") (pin "2") (pinfunction "2_2") (pintype "passive"))
      (node (ref "C54") (pin "2") (pinfunction "2_2") (pintype "passive"))
      (node (ref "C55") (pin "2") (pinfunction "2_2") (pintype "passive"))
      (node (ref "C56") (pin "2") (pinfunction "2_2") (pintype "passive"))
      (node (ref "C57") (pin "2") (pinfunction "2_2") (pintype "passive"))
      (node (ref "C58") (pin "2") (pinfunction "2_2") (pintype "passive"))
      (node (ref "C6") (pin "2") (pinfunction "2_2") (pintype "passive"))
      (node (ref "C7") (pin "2") (pinfunction "2_2") (pintype "passive"))
      (node (ref "C8") (pin "2") (pinfunction "2_2") (pintype "passive"))
      (node (ref "C9") (pin "2") (pinfunction "2_2") (pintype "passive"))
      (node (ref "CM1") (pin "3") (pinfunction "GND_3") (pintype "passive"))
      (node (ref "CM1") (pin "5") (pinfunction "GND_5") (pintype "passive"))
      (node (ref "CM1") (pin "9") (pinfunction "GNDDET_9") (pintype "passive"))
      (node (ref "D1") (pin "A") (pinfunction "A_A") (pintype "passive"))
      (node (ref "D2") (pin "A") (pinfunction "A_A") (pintype "passive"))
      (node (ref "HES1") (pin "2") (pinfunction "2_2") (pintype "passive"))
      (node (ref "HES2") (pin "2") (pinfunction "2_2") (pintype "passive"))
      (node (ref "HES3") (pin "2") (pinfunction "2_2") (pintype "passive"))
      (node (ref "HES4") (pin "2") (pinfunction "2_2") (pintype "passive"))
      (node (ref "HES5") (pin "2") (pinfunction "2_2") (pintype "passive"))
      (node (ref "HES6") (pin "2") (pinfunction "2_2") (pintype "passive"))
      (node (ref "HES7") (pin "2") (pinfunction "2_2") (pintype "passive"))
      (node (ref "HES8") (pin "2") (pinfunction "2_2") (pintype "passive"))
      (node (ref "HES9") (pin "2") (pinfunction "2_2") (pintype "passive"))
      (node (ref "IC1") (pin "11") (pinfunction "I_11") (pintype "input"))
      (node (ref "IC1") (pin "14") (pinfunction "I_14") (pintype "input"))
      (node (ref "IC1") (pin "8") (pinfunction "VSS_8") (pintype "power_in"))
      (node (ref "JP2") (pin "17") (pinfunction "17_17") (pintype "passive"))
      (node (ref "JP2") (pin "19") (pinfunction "19_19") (pintype "passive"))
      (node (ref "JP2") (pin "31") (pinfunction "31_31") (pintype "passive"))
      (node (ref "JP2") (pin "32") (pinfunction "32_32") (pintype "passive"))
      (node (ref "POE.") (pin "C") (pinfunction "C_C") (pintype "passive"))
      (node (ref "POE_IN") (pin "GND") (pinfunction "GNDBREAK_GND") (pintype "power_in"))
      (node (ref "POE_IN") (pin "GNDBREAK") (pinfunction "GND_GNDBREAK") (pintype "power_in"))
      (node (ref "Q1") (pin "2") (pinfunction "S_2") (pintype "passive"))
      (node (ref "Q2") (pin "2") (pinfunction "S_2") (pintype "passive"))
      (node (ref "Q3") (pin "2") (pinfunction "S_2") (pintype "passive"))
      (node (ref "Q4") (pin "2") (pinfunction "S_2") (pintype "passive"))
      (node (ref "Q6") (pin "2") (pinfunction "S_2") (pintype "passive"))
      (node (ref "R15") (pin "1") (pinfunction "1_1") (pintype "passive"))
      (node (ref "R16") (pin "1") (pinfunction "1_1") (pintype "passive"))
      (node (ref "R17") (pin "1") (pinfunction "1_1") (pintype "passive"))
      (node (ref "R18") (pin "1") (pinfunction "1_1") (pintype "passive"))
      (node (ref "R1_H") (pin "1") (pinfunction "1_1") (pintype "passive"))
      (node (ref "R1_L") (pin "1") (pinfunction "1_1") (pintype "passive"))
      (node (ref "R20") (pin "1") (pinfunction "1_1") (pintype "passive"))
      (node (ref "SM_STAT") (pin "3") (pinfunction "3_3") (pintype "passive"))
      (node (ref "U1") (pin "4") (pinfunction "GND_4") (pintype "passive"))
      (node (ref "U2") (pin "4") (pinfunction "GND_4") (pintype "passive"))
      (node (ref "U4") (pin "12") (pinfunction "VSSA/VREF-_12") (pintype "power_in"))
      (node (ref "U4") (pin "18") (pinfunction "VSS_2_18") (pintype "power_in"))
      (node (ref "U4") (pin "31") (pinfunction "VSS_3_31") (pintype "power_in"))
      (node (ref "U4") (pin "47") (pinfunction "VSS_4_47") (pintype "power_in"))
      (node (ref "U4") (pin "63") (pinfunction "VSS_63") (pintype "power_in"))
      (node (ref "X1") (pin "2") (pinfunction "SHIELD_2") (pintype "power_in"))
      (node (ref "X1") (pin "4") (pinfunction "SHIELD_4") (pintype "power_in"))
      (node (ref "X2") (pin "6") (pinfunction "VSS_6") (pintype "power_in"))
      (node (ref "X2") (pin "MT1") (pinfunction "GND_MT1") (pintype "power_in"))
      (node (ref "X2") (pin "MT2") (pinfunction "GND1_MT2") (pintype "power_in"))
    )
    (net (code "6") (name "IN_CTS") (class "Default")
      (node (ref "SM_STAT") (pin "4") (pinfunction "4_4") (pintype "passive"))
      (node (ref "U4") (pin "44") (pinfunction "PA11_44") (pintype "bidirectional"))
    )
    (net (code "7") (name "IN_H1") (class "Default")
      (node (ref "C1") (pin "1") (pinfunction "1_1") (pintype "passive"))
      (node (ref "HES1") (pin "3") (pinfunction "3_3") (pintype "passive"))
      (node (ref "JP3") (pin "1") (pinfunction "1_1") (pintype "passive"))
      (node (ref "R1") (pin "2") (pinfunction "2_2") (pintype "passive"))
      (node (ref "U4") (pin "15") (pinfunction "PA1_15") (pintype "bidirectional"))
    )
    (net (code "8") (name "IN_H2") (class "Default")
      (node (ref "C2") (pin "1") (pinfunction "1_1") (pintype "passive"))
      (node (ref "HES2") (pin "3") (pinfunction "3_3") (pintype "passive"))
      (node (ref "JP3") (pin "2") (pinfunction "2_2") (pintype "passive"))
      (node (ref "R2") (pin "2") (pinfunction "2_2") (pintype "passive"))
      (node (ref "U4") (pin "16") (pinfunction "PA2_16") (pintype "bidirectional"))
    )
    (net (code "9") (name "IN_H3") (class "Default")
      (node (ref "C3") (pin "1") (pinfunction "1_1") (pintype "passive"))
      (node (ref "HES3") (pin "3") (pinfunction "3_3") (pintype "passive"))
      (node (ref "JP3") (pin "3") (pinfunction "3_3") (pintype "passive"))
      (node (ref "R3") (pin "2") (pinfunction "2_2") (pintype "passive"))
      (node (ref "U4") (pin "17") (pinfunction "PA3_17") (pintype "bidirectional"))
    )
    (net (code "10") (name "IN_H4") (class "Default")
      (node (ref "C4") (pin "1") (pinfunction "1_1") (pintype "passive"))
      (node (ref "HES4") (pin "3") (pinfunction "3_3") (pintype "passive"))
      (node (ref "JP3") (pin "4") (pinfunction "4_4") (pintype "passive"))
      (node (ref "R4") (pin "2") (pinfunction "2_2") (pintype "passive"))
      (node (ref "U4") (pin "20") (pinfunction "PA4_20") (pintype "bidirectional"))
    )
    (net (code "11") (name "IN_H5") (class "Default")
      (node (ref "C5") (pin "1") (pinfunction "1_1") (pintype "passive"))
      (node (ref "HES5") (pin "3") (pinfunction "3_3") (pintype "passive"))
      (node (ref "JP3") (pin "5") (pinfunction "5_5") (pintype "passive"))
      (node (ref "R5") (pin "2") (pinfunction "2_2") (pintype "passive"))
      (node (ref "U4") (pin "59") (pinfunction "PB7_59") (pintype "bidirectional"))
    )
    (net (code "12") (name "IN_H6") (class "Default")
      (node (ref "C6") (pin "1") (pinfunction "1_1") (pintype "passive"))
      (node (ref "HES6") (pin "3") (pinfunction "3_3") (pintype "passive"))
      (node (ref "JP3") (pin "6") (pinfunction "6_6") (pintype "passive"))
      (node (ref "R6") (pin "2") (pinfunction "2_2") (pintype "passive"))
      (node (ref "U4") (pin "58") (pinfunction "PB6_58") (pintype "bidirectional"))
    )
    (net (code "13") (name "IN_H7") (class "Default")
      (node (ref "C7") (pin "1") (pinfunction "1_1") (pintype "passive"))
      (node (ref "HES7") (pin "3") (pinfunction "3_3") (pintype "passive"))
      (node (ref "JP3") (pin "7") (pinfunction "7_7") (pintype "passive"))
      (node (ref "R7") (pin "2") (pinfunction "2_2") (pintype "passive"))
      (node (ref "U4") (pin "50") (pinfunction "PA15_50") (pintype "bidirectional"))
    )
    (net (code "14") (name "IN_H8") (class "Default")
      (node (ref "C8") (pin "1") (pinfunction "1_1") (pintype "passive"))
      (node (ref "HES8") (pin "3") (pinfunction "3_3") (pintype "passive"))
      (node (ref "JP3") (pin "8") (pinfunction "8_8") (pintype "passive"))
      (node (ref "R8") (pin "2") (pinfunction "2_2") (pintype "passive"))
      (node (ref "U4") (pin "41") (pinfunction "PA8_41") (pintype "bidirectional"))
    )
    (net (code "15") (name "IN_H9") (class "Default")
      (node (ref "C9") (pin "1") (pinfunction "1_1") (pintype "passive"))
      (node (ref "HES9") (pin "3") (pinfunction "3_3") (pintype "passive"))
      (node (ref "JP3") (pin "9") (pinfunction "9_9") (pintype "passive"))
      (node (ref "R9") (pin "2") (pinfunction "2_2") (pintype "passive"))
      (node (ref "U4") (pin "14") (pinfunction "PA0_14") (pintype "bidirectional"))
    )
    (net (code "16") (name "IN_RTS") (class "Default")
      (node (ref "SM_STAT") (pin "5") (pinfunction "5_5") (pintype "passive"))
      (node (ref "U4") (pin "45") (pinfunction "PA12_45") (pintype "bidirectional"))
    )
    (net (code "17") (name "IN_UART-RX") (class "Default")
      (node (ref "R14") (pin "2") (pinfunction "2_2") (pintype "passive"))
      (node (ref "U4") (pin "43") (pinfunction "PA10_43") (pintype "bidirectional"))
    )
    (net (code "18") (name "IN_UART-TX") (class "Default")
      (node (ref "SM_STAT") (pin "1") (pinfunction "1_1") (pintype "passive"))
      (node (ref "U4") (pin "42") (pinfunction "PA9_42") (pintype "bidirectional"))
    )
    (net (code "19") (name "LED0") (class "Default")
      (node (ref "JP1") (pin "9") (pinfunction "9_9") (pintype "passive"))
      (node (ref "R21") (pin "2") (pinfunction "2_2") (pintype "passive"))
    )
    (net (code "20") (name "LED1") (class "Default")
      (node (ref "JP1") (pin "7") (pinfunction "7_7") (pintype "passive"))
      (node (ref "R10") (pin "2") (pinfunction "2_2") (pintype "passive"))
    )
    (net (code "21") (name "LED2") (class "Default")
      (node (ref "JP1") (pin "5") (pinfunction "5_5") (pintype "passive"))
      (node (ref "R11") (pin "2") (pinfunction "2_2") (pintype "passive"))
    )
    (net (code "22") (name "LED3") (class "Default")
      (node (ref "JP1") (pin "3") (pinfunction "3_3") (pintype "passive"))
      (node (ref "R12") (pin "2") (pinfunction "2_2") (pintype "passive"))
    )
    (net (code "23") (name "Net-(3V3.-PadA)") (class "Default")
      (node (ref "3V3.") (pin "A") (pinfunction "A_A") (pintype "passive"))
      (node (ref "R26") (pin "1") (pinfunction "1_1") (pintype "passive"))
    )
    (net (code "24") (name "Net-(10V.-PadA)") (class "Default")
      (node (ref "10V.") (pin "A") (pinfunction "A_A") (pintype "passive"))
      (node (ref "R27") (pin "1") (pinfunction "1_1") (pintype "passive"))
    )
    (net (code "25") (name "Net-(BATT-Pad1)") (class "Default")
      (node (ref "BATT") (pin "1") (pinfunction "1_1") (pintype "passive"))
      (node (ref "D6") (pin "A") (pinfunction "A_A") (pintype "passive"))
    )
    (net (code "26") (name "Net-(CM1-SWDCLK{slash}TCK)") (class "Default")
      (node (ref "CM1") (pin "4") (pinfunction "SWDCLK/TCK_4") (pintype "passive"))
      (node (ref "U4") (pin "49") (pinfunction "PA14_49") (pintype "bidirectional"))
    )
    (net (code "27") (name "Net-(CM1-SWDIO{slash}TMS)") (class "Default")
      (node (ref "CM1") (pin "2") (pinfunction "SWDIO/TMS_2") (pintype "passive"))
      (node (ref "U4") (pin "46") (pinfunction "PA13_46") (pintype "bidirectional"))
    )
    (net (code "28") (name "Net-(CM1-~{RESET})") (class "Default")
      (node (ref "CM1") (pin "10") (pinfunction "~{RESET}_10") (pintype "passive"))
      (node (ref "U4") (pin "7") (pinfunction "NRST_7") (pintype "bidirectional"))
    )
    (net (code "29") (name "Net-(IC1A-O)") (class "Default")
      (node (ref "IC1") (pin "2") (pinfunction "O_2") (pintype "output"))
      (node (ref "X2") (pin "5") (pinfunction "SCLK_5") (pintype "input"))
    )
    (net (code "30") (name "Net-(IC1B-O)") (class "Default")
      (node (ref "IC1") (pin "4") (pinfunction "O_4") (pintype "output"))
      (node (ref "X2") (pin "3") (pinfunction "DATA_IN_3") (pintype "input"))
    )
    (net (code "31") (name "Net-(IC1C-O)") (class "Default")
      (node (ref "IC1") (pin "6") (pinfunction "O_6") (pintype "output"))
      (node (ref "R23") (pin "1") (pinfunction "1_1") (pintype "passive"))
      (node (ref "X2") (pin "2") (pinfunction "CS_2") (pintype "input"))
    )
    (net (code "32") (name "Net-(IC1D-O)") (class "Default")
      (node (ref "IC1") (pin "10") (pinfunction "O_10") (pintype "output"))
      (node (ref "SD") (pin "A") (pinfunction "A_A") (pintype "passive"))
    )
    (net (code "33") (name "Net-(POE.-PadA)") (class "Default")
      (node (ref "POE.") (pin "A") (pinfunction "A_A") (pintype "passive"))
      (node (ref "R25") (pin "1") (pinfunction "1_1") (pintype "passive"))
    )
    (net (code "34") (name "Net-(POE_IN-PWR)") (class "Default")
      (node (ref "D5") (pin "A") (pinfunction "A_A") (pintype "passive"))
      (node (ref "POE_IN") (pin "PWR1") (pinfunction "PWR_PWR1") (pintype "power_in"))
      (node (ref "R25") (pin "2") (pinfunction "2_2") (pintype "passive"))
    )
    (net (code "35") (name "Net-(Q1-D)") (class "Default")
      (node (ref "Q1") (pin "3") (pinfunction "D_3") (pintype "passive"))
      (node (ref "R10") (pin "1") (pinfunction "1_1") (pintype "passive"))
    )
    (net (code "36") (name "Net-(Q2-D)") (class "Default")
      (node (ref "Q2") (pin "3") (pinfunction "D_3") (pintype "passive"))
      (node (ref "R11") (pin "1") (pinfunction "1_1") (pintype "passive"))
    )
    (net (code "37") (name "Net-(Q3-D)") (class "Default")
      (node (ref "Q3") (pin "3") (pinfunction "D_3") (pintype "passive"))
      (node (ref "R12") (pin "1") (pinfunction "1_1") (pintype "passive"))
    )
    (net (code "38") (name "Net-(Q4-D)") (class "Default")
      (node (ref "Q4") (pin "3") (pinfunction "D_3") (pintype "passive"))
      (node (ref "R13") (pin "1") (pinfunction "1_1") (pintype "passive"))
    )
    (net (code "39") (name "Net-(Q6-D)") (class "Default")
      (node (ref "Q6") (pin "3") (pinfunction "D_3") (pintype "passive"))
      (node (ref "R21") (pin "1") (pinfunction "1_1") (pintype "passive"))
    )
    (net (code "40") (name "Net-(R14-Pad1)") (class "Default")
      (node (ref "R14") (pin "1") (pinfunction "1_1") (pintype "passive"))
      (node (ref "SM_STAT") (pin "2") (pinfunction "2_2") (pintype "passive"))
    )
    (net (code "41") (name "Net-(R23-Pad2)") (class "Default")
      (node (ref "R23") (pin "2") (pinfunction "2_2") (pintype "passive"))
      (node (ref "SD") (pin "C") (pinfunction "C_C") (pintype "passive"))
    )
    (net (code "42") (name "Net-(U1-COMPARATORINVERTINGINPUT)") (class "Default")
      (node (ref "R1_L") (pin "2") (pinfunction "2_2") (pintype "passive"))
      (node (ref "R2_L") (pin "1") (pinfunction "1_1") (pintype "passive"))
      (node (ref "U1") (pin "5") (pinfunction "COMPARATORINVERTINGINPUT_5") (pintype "passive"))
    )
    (net (code "43") (name "Net-(U1-DRIVERCOLLECTOR)") (class "Default")
      (node (ref "RS_L") (pin "1") (pinfunction "1_1") (pintype "passive"))
      (node (ref "U1") (pin "1") (pinfunction "SWITCHCOLLECTOR_1") (pintype "passive"))
      (node (ref "U1") (pin "7") (pinfunction "IPK_7") (pintype "passive"))
      (node (ref "U1") (pin "8") (pinfunction "DRIVERCOLLECTOR_8") (pintype "passive"))
    )
    (net (code "44") (name "Net-(U1-SWITCHEMITTER)") (class "Default")
      (node (ref "D1") (pin "C") (pinfunction "C_C") (pintype "passive"))
      (node (ref "L1") (pin "1") (pinfunction "1_1") (pintype "passive"))
      (node (ref "U1") (pin "2") (pinfunction "SWITCHEMITTER_2") (pintype "passive"))
    )
    (net (code "45") (name "Net-(U1-TIMINGCAPACITOR)") (class "Default")
      (node (ref "C2_L") (pin "1") (pinfunction "1_1") (pintype "passive"))
      (node (ref "U1") (pin "3") (pinfunction "TIMINGCAPACITOR_3") (pintype "passive"))
    )
    (net (code "46") (name "Net-(U1-VCC)") (class "Default")
      (node (ref "C13") (pin "1") (pinfunction "1_1") (pintype "passive"))
      (node (ref "C14") (pin "1") (pinfunction "1_1") (pintype "passive"))
      (node (ref "C15") (pin "1") (pinfunction "1_1") (pintype "passive"))
      (node (ref "C16") (pin "1") (pinfunction "1_1") (pintype "passive"))
      (node (ref "C17") (pin "1") (pinfunction "1_1") (pintype "passive"))
      (node (ref "C18") (pin "1") (pinfunction "1_1") (pintype "passive"))
      (node (ref "C19") (pin "1") (pinfunction "1_1") (pintype "passive"))
      (node (ref "C20") (pin "1") (pinfunction "1_1") (pintype "passive"))
      (node (ref "C21") (pin "1") (pinfunction "1_1") (pintype "passive"))
      (node (ref "C22") (pin "1") (pinfunction "1_1") (pintype "passive"))
      (node (ref "C34") (pin "1") (pinfunction "1_1") (pintype "passive"))
      (node (ref "C35") (pin "1") (pinfunction "1_1") (pintype "passive"))
      (node (ref "C36") (pin "1") (pinfunction "1_1") (pintype "passive"))
      (node (ref "C37") (pin "1") (pinfunction "1_1") (pintype "passive"))
      (node (ref "C38") (pin "1") (pinfunction "1_1") (pintype "passive"))
      (node (ref "C39") (pin "1") (pinfunction "1_1") (pintype "passive"))
      (node (ref "C40") (pin "1") (pinfunction "1_1") (pintype "passive"))
      (node (ref "C41") (pin "1") (pinfunction "1_1") (pintype "passive"))
      (node (ref "C42") (pin "1") (pinfunction "1_1") (pintype "passive"))
      (node (ref "C43") (pin "1") (pinfunction "1_1") (pintype "passive"))
      (node (ref "D5") (pin "C") (pinfunction "C_C") (pintype "passive"))
      (node (ref "D6") (pin "C") (pinfunction "C_C") (pintype "passive"))
      (node (ref "RS_H") (pin "2") (pinfunction "2_2") (pintype "passive"))
      (node (ref "RS_L") (pin "2") (pinfunction "2_2") (pintype "passive"))
      (node (ref "U1") (pin "6") (pinfunction "VCC_6") (pintype "passive"))
      (node (ref "U2") (pin "6") (pinfunction "VCC_6") (pintype "passive"))
    )
    (net (code "47") (name "Net-(U2-COMPARATORINVERTINGINPUT)") (class "Default")
      (node (ref "R1_H") (pin "2") (pinfunction "2_2") (pintype "passive"))
      (node (ref "R2_H") (pin "1") (pinfunction "1_1") (pintype "passive"))
      (node (ref "U2") (pin "5") (pinfunction "COMPARATORINVERTINGINPUT_5") (pintype "passive"))
    )
    (net (code "48") (name "Net-(U2-DRIVERCOLLECTOR)") (class "Default")
      (node (ref "RS_H") (pin "1") (pinfunction "1_1") (pintype "passive"))
      (node (ref "U2") (pin "1") (pinfunction "SWITCHCOLLECTOR_1") (pintype "passive"))
      (node (ref "U2") (pin "7") (pinfunction "IPK_7") (pintype "passive"))
      (node (ref "U2") (pin "8") (pinfunction "DRIVERCOLLECTOR_8") (pintype "passive"))
    )
    (net (code "49") (name "Net-(U2-SWITCHEMITTER)") (class "Default")
      (node (ref "D2") (pin "C") (pinfunction "C_C") (pintype "passive"))
      (node (ref "L2") (pin "1") (pinfunction "1_1") (pintype "passive"))
      (node (ref "U2") (pin "2") (pinfunction "SWITCHEMITTER_2") (pintype "passive"))
    )
    (net (code "50") (name "Net-(U2-TIMINGCAPACITOR)") (class "Default")
      (node (ref "C2_H") (pin "1") (pinfunction "1_1") (pintype "passive"))
      (node (ref "U2") (pin "3") (pinfunction "TIMINGCAPACITOR_3") (pintype "passive"))
    )
    (net (code "51") (name "Net-(U4A-PH0-OSC_IN)") (class "Default")
      (node (ref "C57") (pin "1") (pinfunction "1_1") (pintype "passive"))
      (node (ref "U4") (pin "5") (pinfunction "PH0-OSC_IN_5") (pintype "bidirectional"))
      (node (ref "X1") (pin "3") (pinfunction "2_3") (pintype "passive"))
    )
    (net (code "52") (name "Net-(U4A-PH1-OSC_OUT)") (class "Default")
      (node (ref "C56") (pin "1") (pinfunction "1_1") (pintype "passive"))
      (node (ref "U4") (pin "6") (pinfunction "PH1-OSC_OUT_6") (pintype "bidirectional"))
      (node (ref "X1") (pin "1") (pinfunction "1_1") (pintype "passive"))
    )
    (net (code "53") (name "OUT_BUZZ") (class "Default")
      (node (ref "Q4") (pin "1") (pinfunction "G_1") (pintype "passive"))
      (node (ref "R18") (pin "2") (pinfunction "2_2") (pintype "passive"))
      (node (ref "U4") (pin "26") (pinfunction "PB0_26") (pintype "bidirectional"))
    )
    (net (code "54") (name "OUT_CLK") (class "Default")
      (node (ref "IC1") (pin "3") (pinfunction "I_3") (pintype "input"))
      (node (ref "IC1") (pin "9") (pinfunction "I_9") (pintype "input"))
      (node (ref "U4") (pin "29") (pinfunction "PB10_29") (pintype "bidirectional"))
    )
    (net (code "55") (name "OUT_CS") (class "Default")
      (node (ref "IC1") (pin "7") (pinfunction "I_7") (pintype "input"))
      (node (ref "U4") (pin "27") (pinfunction "PB1_27") (pintype "bidirectional"))
    )
    (net (code "56") (name "OUT_DI") (class "Default")
      (node (ref "IC1") (pin "5") (pinfunction "I_5") (pintype "input"))
      (node (ref "U4") (pin "10") (pinfunction "PC2_10") (pintype "bidirectional"))
    )
    (net (code "57") (name "OUT_DO") (class "Default")
      (node (ref "U4") (pin "11") (pinfunction "PC3_11") (pintype "bidirectional"))
      (node (ref "X2") (pin "7") (pinfunction "DATA_OUT_7") (pintype "output"))
    )
    (net (code "58") (name "OUT_LED0") (class "Default")
      (node (ref "Q6") (pin "1") (pinfunction "G_1") (pintype "passive"))
      (node (ref "R20") (pin "2") (pinfunction "2_2") (pintype "passive"))
      (node (ref "U4") (pin "61") (pinfunction "PB8_61") (pintype "bidirectional"))
    )
    (net (code "59") (name "OUT_LED1") (class "Default")
      (node (ref "Q1") (pin "1") (pinfunction "G_1") (pintype "passive"))
      (node (ref "R15") (pin "2") (pinfunction "2_2") (pintype "passive"))
      (node (ref "U4") (pin "57") (pinfunction "PB5_57") (pintype "bidirectional"))
    )
    (net (code "60") (name "OUT_LED2") (class "Default")
      (node (ref "Q2") (pin "1") (pinfunction "G_1") (pintype "passive"))
      (node (ref "R16") (pin "2") (pinfunction "2_2") (pintype "passive"))
      (node (ref "U4") (pin "56") (pinfunction "PB4_56") (pintype "bidirectional"))
    )
    (net (code "61") (name "OUT_LED3") (class "Default")
      (node (ref "Q3") (pin "1") (pinfunction "G_1") (pintype "passive"))
      (node (ref "R17") (pin "2") (pinfunction "2_2") (pintype "passive"))
      (node (ref "U4") (pin "55") (pinfunction "PB3_55") (pintype "bidirectional"))
    )
    (net (code "62") (name "PA_5") (class "Default")
      (node (ref "U4") (pin "21") (pinfunction "PA5_21") (pintype "bidirectional"))
    )
    (net (code "63") (name "PA_6") (class "Default")
      (node (ref "U4") (pin "22") (pinfunction "PA6_22") (pintype "bidirectional"))
    )
    (net (code "64") (name "PA_7") (class "Default")
      (node (ref "U4") (pin "23") (pinfunction "PA7_23") (pintype "bidirectional"))
    )
    (net (code "65") (name "PB2") (class "Default")
      (node (ref "JP2") (pin "1") (pinfunction "1_1") (pintype "passive"))
      (node (ref "U4") (pin "28") (pinfunction "PB2_28") (pintype "bidirectional"))
    )
    (net (code "66") (name "PB9") (class "Default")
      (node (ref "JP2") (pin "26") (pinfunction "26_26") (pintype "passive"))
      (node (ref "U4") (pin "62") (pinfunction "PB9_62") (pintype "bidirectional"))
    )
    (net (code "67") (name "PB10") (class "Default")
      (node (ref "JP2") (pin "3") (pinfunction "3_3") (pintype "passive"))
    )
    (net (code "68") (name "PB11") (class "Default")
      (node (ref "JP2") (pin "5") (pinfunction "5_5") (pintype "passive"))
      (node (ref "U4") (pin "30") (pinfunction "PB11_30") (pintype "bidirectional"))
    )
    (net (code "69") (name "PB12") (class "Default")
      (node (ref "JP2") (pin "7") (pinfunction "7_7") (pintype "passive"))
      (node (ref "U4") (pin "33") (pinfunction "PB12_33") (pintype "bidirectional"))
    )
    (net (code "70") (name "PB13") (class "Default")
      (node (ref "JP2") (pin "9") (pinfunction "9_9") (pintype "passive"))
      (node (ref "U4") (pin "34") (pinfunction "PB13_34") (pintype "bidirectional"))
    )
    (net (code "71") (name "PB14") (class "Default")
      (node (ref "JP2") (pin "11") (pinfunction "11_11") (pintype "passive"))
      (node (ref "U4") (pin "35") (pinfunction "PB14_35") (pintype "bidirectional"))
    )
    (net (code "72") (name "PB15") (class "Default")
      (node (ref "JP2") (pin "13") (pinfunction "13_13") (pintype "passive"))
      (node (ref "U4") (pin "36") (pinfunction "PB15_36") (pintype "bidirectional"))
    )
    (net (code "73") (name "PC0") (class "Default")
      (node (ref "JP2") (pin "28") (pinfunction "28_28") (pintype "passive"))
      (node (ref "U4") (pin "8") (pinfunction "PC0_8") (pintype "bidirectional"))
    )
    (net (code "74") (name "PC1") (class "Default")
      (node (ref "JP2") (pin "8") (pinfunction "8_8") (pintype "passive"))
      (node (ref "U4") (pin "9") (pinfunction "PC1_9") (pintype "bidirectional"))
    )
    (net (code "75") (name "PC2") (class "Default")
      (node (ref "JP2") (pin "30") (pinfunction "30_30") (pintype "passive"))
    )
    (net (code "76") (name "PC3") (class "Default")
      (node (ref "JP2") (pin "22") (pinfunction "22_22") (pintype "passive"))
    )
    (net (code "77") (name "PC4") (class "Default")
      (node (ref "JP2") (pin "12") (pinfunction "12_12") (pintype "passive"))
      (node (ref "U4") (pin "24") (pinfunction "PC4_24") (pintype "bidirectional"))
    )
    (net (code "78") (name "PC5") (class "Default")
      (node (ref "JP2") (pin "14") (pinfunction "14_14") (pintype "passive"))
      (node (ref "U4") (pin "25") (pinfunction "PC5_25") (pintype "bidirectional"))
    )
    (net (code "79") (name "PC6") (class "Default")
      (node (ref "JP2") (pin "16") (pinfunction "16_16") (pintype "passive"))
      (node (ref "U4") (pin "37") (pinfunction "PC6_37") (pintype "bidirectional"))
    )
    (net (code "80") (name "PC7") (class "Default")
      (node (ref "JP2") (pin "18") (pinfunction "18_18") (pintype "passive"))
      (node (ref "U4") (pin "38") (pinfunction "PC7_38") (pintype "bidirectional"))
    )
    (net (code "81") (name "PC8") (class "Default")
      (node (ref "JP2") (pin "6") (pinfunction "6_6") (pintype "passive"))
      (node (ref "U4") (pin "39") (pinfunction "PC8_39") (pintype "bidirectional"))
    )
    (net (code "82") (name "PC9") (class "Default")
      (node (ref "JP2") (pin "4") (pinfunction "4_4") (pintype "passive"))
      (node (ref "U4") (pin "40") (pinfunction "PC9_40") (pintype "bidirectional"))
    )
    (net (code "83") (name "PC10") (class "Default")
      (node (ref "JP2") (pin "10") (pinfunction "10_10") (pintype "passive"))
      (node (ref "U4") (pin "51") (pinfunction "PC10_51") (pintype "bidirectional"))
    )
    (net (code "84") (name "PC11") (class "Default")
      (node (ref "JP2") (pin "15") (pinfunction "15_15") (pintype "passive"))
      (node (ref "U4") (pin "52") (pinfunction "PC11_52") (pintype "bidirectional"))
    )
    (net (code "85") (name "PC12") (class "Default")
      (node (ref "JP2") (pin "20") (pinfunction "20_20") (pintype "passive"))
      (node (ref "U4") (pin "53") (pinfunction "PC12_53") (pintype "bidirectional"))
    )
    (net (code "86") (name "PC13") (class "Default")
      (node (ref "JP2") (pin "25") (pinfunction "25_25") (pintype "passive"))
      (node (ref "U4") (pin "2") (pinfunction "PC13_2") (pintype "bidirectional"))
    )
    (net (code "87") (name "PC14-OSC32_IN") (class "Default")
      (node (ref "JP2") (pin "23") (pinfunction "23_23") (pintype "passive"))
      (node (ref "U4") (pin "3") (pinfunction "PC14-OSC32_IN_3") (pintype "bidirectional"))
    )
    (net (code "88") (name "PC15-OSC32_OUT") (class "Default")
      (node (ref "JP2") (pin "29") (pinfunction "29_29") (pintype "passive"))
      (node (ref "U4") (pin "4") (pinfunction "PC15-OSC32_OUT_4") (pintype "bidirectional"))
    )
    (net (code "89") (name "PD2") (class "Default")
      (node (ref "JP2") (pin "21") (pinfunction "21_21") (pintype "passive"))
      (node (ref "U4") (pin "54") (pinfunction "PD2_54") (pintype "bidirectional"))
    )
    (net (code "90") (name "VBATT") (class "Default")
      (node (ref "C54") (pin "1") (pinfunction "1_1") (pintype "passive"))
      (node (ref "U4") (pin "1") (pinfunction "VBAT_1") (pintype "power_in"))
    )
    (net (code "91") (name "unconnected-(CM1-NC{slash}TDI-Pad8)") (class "Default")
      (node (ref "CM1") (pin "8") (pinfunction "NC/TDI_8") (pintype "passive"))
    )
    (net (code "92") (name "unconnected-(CM1-SWO{slash}TDO-Pad6)") (class "Default")
      (node (ref "CM1") (pin "6") (pinfunction "SWO/TDO_6") (pintype "passive"))
    )
    (net (code "93") (name "unconnected-(IC1E-O-Pad12)") (class "Default")
      (node (ref "IC1") (pin "12") (pinfunction "O_12") (pintype "output"))
    )
    (net (code "94") (name "unconnected-(IC1F-O-Pad15)") (class "Default")
      (node (ref "IC1") (pin "15") (pinfunction "O_15") (pintype "output"))
    )
    (net (code "95") (name "unconnected-(JP3-Pad10)") (class "Default")
      (node (ref "JP3") (pin "10") (pinfunction "10_10") (pintype "passive"))
    )
    (net (code "96") (name "unconnected-(JP3-Pad11)") (class "Default")
      (node (ref "JP3") (pin "11") (pinfunction "11_11") (pintype "passive"))
    )
    (net (code "97") (name "unconnected-(JP3-Pad12)") (class "Default")
      (node (ref "JP3") (pin "12") (pinfunction "12_12") (pintype "passive"))
    )
    (net (code "98") (name "unconnected-(X2-CARD_DETECT-PadCD1)") (class "Default")
      (node (ref "X2") (pin "CD1") (pinfunction "CARD_DETECT_CD1") (pintype "passive"))
    )
    (net (code "99") (name "unconnected-(X2-CARD_DETECT1-PadCD2)") (class "Default")
      (node (ref "X2") (pin "CD2") (pinfunction "CARD_DETECT1_CD2") (pintype "passive"))
    )
    (net (code "100") (name "unconnected-(X2-DAT1-Pad8)") (class "Default")
      (node (ref "X2") (pin "8") (pinfunction "DAT1_8") (pintype "bidirectional"))
    )
    (net (code "101") (name "unconnected-(X2-DAT2-Pad1)") (class "Default")
      (node (ref "X2") (pin "1") (pinfunction "DAT2_1") (pintype "bidirectional"))
    )
  )
)
